# RAMBo.net
KiCad netlist of a schematic drawn in EAGLE
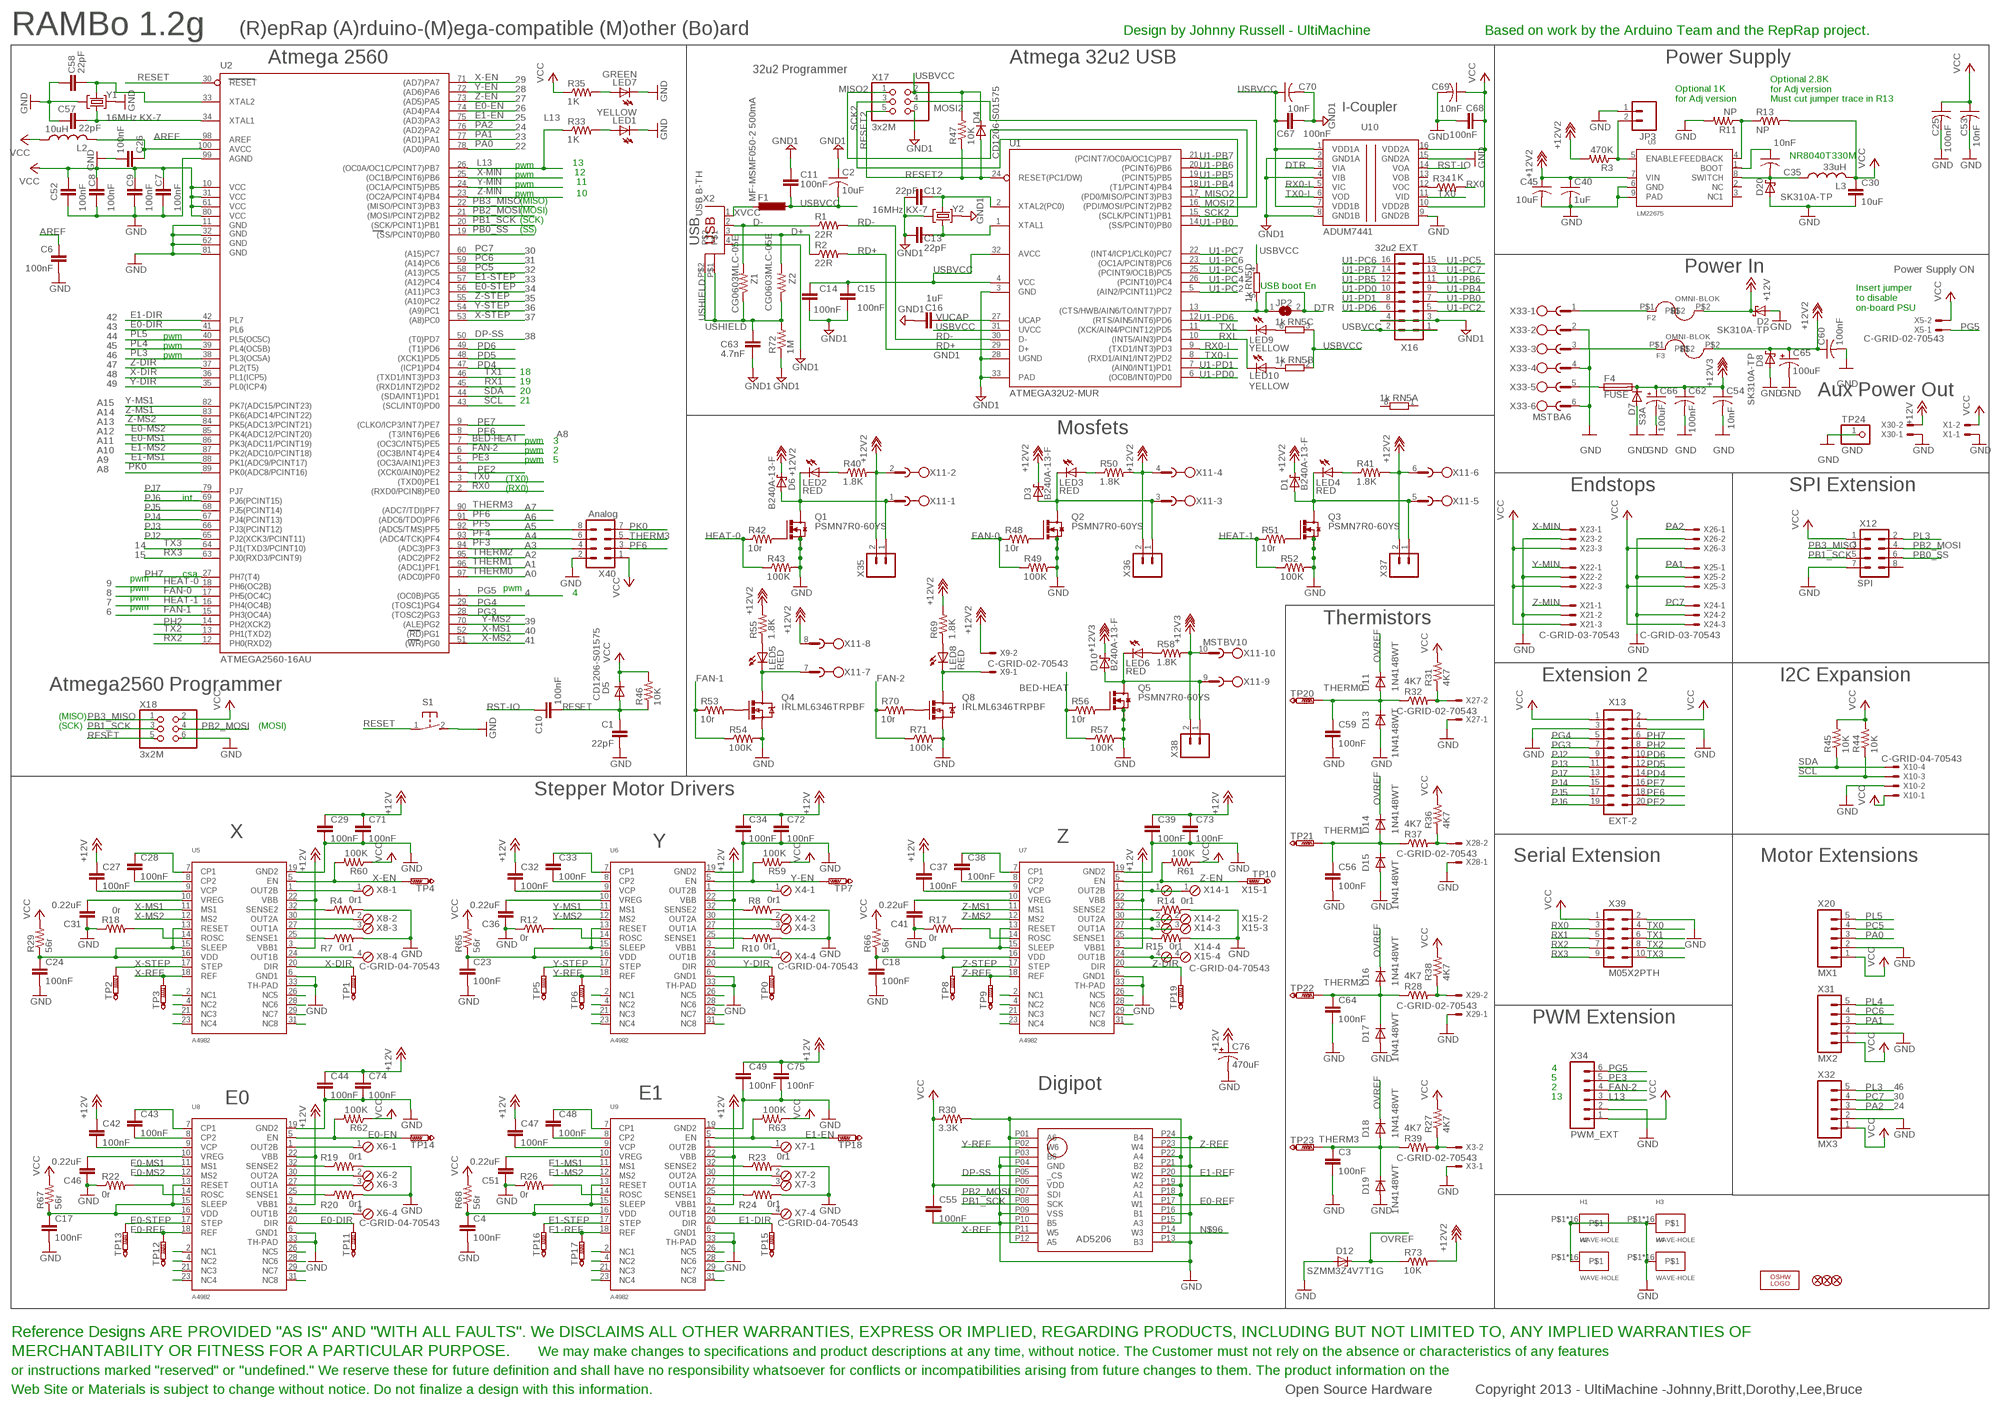
[diagram p0: schematic, sheet 1]

(export (version "E")
  (design (tool "Eeschema 10.0.6"))
  (components
    (comp (ref "C1")
      (value "22pF")
      (footprint "eagle-import:C0603")
      (libsource (lib "eagle-import") (part "resistor_C-EUC0603"))
    )
    (comp (ref "C2")
      (value "10uF")
      (footprint "eagle-import:C0805")
      (libsource (lib "eagle-import") (part "C-USC0805"))
    )
    (comp (ref "C3")
      (value "100nF")
      (footprint "eagle-import:C0603")
      (libsource (lib "eagle-import") (part "resistor_C-EUC0603"))
    )
    (comp (ref "C4")
      (value "100nF")
      (footprint "eagle-import:C0603")
      (libsource (lib "eagle-import") (part "resistor_C-EUC0603"))
    )
    (comp (ref "C6")
      (value "100nF")
      (footprint "eagle-import:C0603")
      (libsource (lib "eagle-import") (part "resistor_C-EUC0603"))
    )
    (comp (ref "C7")
      (value "100nF")
      (footprint "eagle-import:C0603")
      (libsource (lib "eagle-import") (part "resistor_C-EUC0603"))
    )
    (comp (ref "C8")
      (value "100nF")
      (footprint "eagle-import:C0603")
      (libsource (lib "eagle-import") (part "resistor_C-EUC0603"))
    )
    (comp (ref "C9")
      (value "100nF")
      (footprint "eagle-import:C0603")
      (libsource (lib "eagle-import") (part "resistor_C-EUC0603"))
    )
    (comp (ref "C10")
      (value "100nF")
      (footprint "eagle-import:C0603")
      (libsource (lib "eagle-import") (part "resistor_C-EUC0603"))
    )
    (comp (ref "C11")
      (value "100nF")
      (footprint "eagle-import:C0603")
      (libsource (lib "eagle-import") (part "resistor_C-EUC0603"))
    )
    (comp (ref "C12")
      (value "22pF")
      (footprint "eagle-import:C0603")
      (libsource (lib "eagle-import") (part "resistor_C-EUC0603"))
    )
    (comp (ref "C13")
      (value "22pF")
      (footprint "eagle-import:C0603")
      (libsource (lib "eagle-import") (part "resistor_C-EUC0603"))
    )
    (comp (ref "C14")
      (value "100nF")
      (footprint "eagle-import:C0603")
      (libsource (lib "eagle-import") (part "resistor_C-EUC0603"))
    )
    (comp (ref "C15")
      (value "100nF")
      (footprint "eagle-import:C0603")
      (libsource (lib "eagle-import") (part "resistor_C-EUC0603"))
    )
    (comp (ref "C16")
      (value "1uF")
      (footprint "eagle-import:C0603")
      (libsource (lib "eagle-import") (part "resistor_C-EUC0603"))
    )
    (comp (ref "C17")
      (value "100nF")
      (footprint "eagle-import:C0603")
      (libsource (lib "eagle-import") (part "resistor_C-EUC0603"))
    )
    (comp (ref "C18")
      (value "100nF")
      (footprint "eagle-import:C0603")
      (libsource (lib "eagle-import") (part "resistor_C-EUC0603"))
    )
    (comp (ref "C23")
      (value "100nF")
      (footprint "eagle-import:C0603")
      (libsource (lib "eagle-import") (part "resistor_C-EUC0603"))
    )
    (comp (ref "C24")
      (value "100nF")
      (footprint "eagle-import:C0603")
      (libsource (lib "eagle-import") (part "resistor_C-EUC0603"))
    )
    (comp (ref "C25")
      (value "100nF")
      (footprint "eagle-import:C0603")
      (libsource (lib "eagle-import") (part "C-USC0603"))
    )
    (comp (ref "C26")
      (value "100nF")
      (footprint "eagle-import:C0603")
      (libsource (lib "eagle-import") (part "resistor_C-EUC0603"))
    )
    (comp (ref "C27")
      (value "100nF")
      (footprint "eagle-import:C0603")
      (libsource (lib "eagle-import") (part "resistor_C-EUC0603"))
    )
    (comp (ref "C28")
      (value "100nF")
      (footprint "eagle-import:C0603")
      (libsource (lib "eagle-import") (part "resistor_C-EUC0603"))
    )
    (comp (ref "C29")
      (value "100nF")
      (footprint "eagle-import:C0603")
      (libsource (lib "eagle-import") (part "resistor_C-EUC0603"))
    )
    (comp (ref "C30")
      (value "10uF")
      (footprint "eagle-import:C1210K")
      (libsource (lib "eagle-import") (part "resistor_C-EUC1210K"))
    )
    (comp (ref "C31")
      (value "0.22uF")
      (footprint "eagle-import:C0603")
      (libsource (lib "eagle-import") (part "resistor_C-EUC0603"))
    )
    (comp (ref "C32")
      (value "100nF")
      (footprint "eagle-import:C0603")
      (libsource (lib "eagle-import") (part "resistor_C-EUC0603"))
    )
    (comp (ref "C33")
      (value "100nF")
      (footprint "eagle-import:C0603")
      (libsource (lib "eagle-import") (part "resistor_C-EUC0603"))
    )
    (comp (ref "C34")
      (value "100nF")
      (footprint "eagle-import:C0603")
      (libsource (lib "eagle-import") (part "resistor_C-EUC0603"))
    )
    (comp (ref "C35")
      (value "10nF")
      (footprint "eagle-import:C0603")
      (libsource (lib "eagle-import") (part "C-USC0603"))
    )
    (comp (ref "C36")
      (value "0.22uF")
      (footprint "eagle-import:C0603")
      (libsource (lib "eagle-import") (part "resistor_C-EUC0603"))
    )
    (comp (ref "C37")
      (value "100nF")
      (footprint "eagle-import:C0603")
      (libsource (lib "eagle-import") (part "resistor_C-EUC0603"))
    )
    (comp (ref "C38")
      (value "100nF")
      (footprint "eagle-import:C0603")
      (libsource (lib "eagle-import") (part "resistor_C-EUC0603"))
    )
    (comp (ref "C39")
      (value "100nF")
      (footprint "eagle-import:C0603")
      (libsource (lib "eagle-import") (part "resistor_C-EUC0603"))
    )
    (comp (ref "C40")
      (value "1uF")
      (footprint "eagle-import:C0805")
      (libsource (lib "eagle-import") (part "C-USC0805"))
    )
    (comp (ref "C41")
      (value "0.22uF")
      (footprint "eagle-import:C0603")
      (libsource (lib "eagle-import") (part "resistor_C-EUC0603"))
    )
    (comp (ref "C42")
      (value "100nF")
      (footprint "eagle-import:C0603")
      (libsource (lib "eagle-import") (part "resistor_C-EUC0603"))
    )
    (comp (ref "C43")
      (value "100nF")
      (footprint "eagle-import:C0603")
      (libsource (lib "eagle-import") (part "resistor_C-EUC0603"))
    )
    (comp (ref "C44")
      (value "100nF")
      (footprint "eagle-import:C0603")
      (libsource (lib "eagle-import") (part "resistor_C-EUC0603"))
    )
    (comp (ref "C45")
      (value "10uF")
      (footprint "eagle-import:C2220K")
      (libsource (lib "eagle-import") (part "C-USC2220K"))
    )
    (comp (ref "C46")
      (value "0.22uF")
      (footprint "eagle-import:C0603")
      (libsource (lib "eagle-import") (part "resistor_C-EUC0603"))
    )
    (comp (ref "C47")
      (value "100nF")
      (footprint "eagle-import:C0603")
      (libsource (lib "eagle-import") (part "resistor_C-EUC0603"))
    )
    (comp (ref "C48")
      (value "100nF")
      (footprint "eagle-import:C0603")
      (libsource (lib "eagle-import") (part "resistor_C-EUC0603"))
    )
    (comp (ref "C49")
      (value "100nF")
      (footprint "eagle-import:C0603")
      (libsource (lib "eagle-import") (part "resistor_C-EUC0603"))
    )
    (comp (ref "C51")
      (value "0.22uF")
      (footprint "eagle-import:C0603")
      (libsource (lib "eagle-import") (part "resistor_C-EUC0603"))
    )
    (comp (ref "C52")
      (value "100nF")
      (footprint "eagle-import:C0603")
      (libsource (lib "eagle-import") (part "resistor_C-EUC0603"))
    )
    (comp (ref "C53")
      (value "10nF")
      (footprint "eagle-import:C0603")
      (libsource (lib "eagle-import") (part "C-USC0603"))
    )
    (comp (ref "C54")
      (value "10nF")
      (footprint "eagle-import:C0603")
      (libsource (lib "eagle-import") (part "C-USC0603"))
    )
    (comp (ref "C55")
      (value "100nF")
      (footprint "eagle-import:C0603")
      (libsource (lib "eagle-import") (part "resistor_C-EUC0603"))
    )
    (comp (ref "C56")
      (value "100nF")
      (footprint "eagle-import:C0603")
      (libsource (lib "eagle-import") (part "resistor_C-EUC0603"))
    )
    (comp (ref "C57")
      (value "22pF")
      (footprint "eagle-import:C0603")
      (libsource (lib "eagle-import") (part "resistor_C-EUC0603"))
    )
    (comp (ref "C58")
      (value "22pF")
      (footprint "eagle-import:C0603")
      (libsource (lib "eagle-import") (part "resistor_C-EUC0603"))
    )
    (comp (ref "C59")
      (value "100nF")
      (footprint "eagle-import:C0603")
      (libsource (lib "eagle-import") (part "resistor_C-EUC0603"))
    )
    (comp (ref "C60")
      (value "100nF")
      (footprint "eagle-import:C0603")
      (libsource (lib "eagle-import") (part "C-USC0603"))
    )
    (comp (ref "C62")
      (value "100nF")
      (footprint "eagle-import:C0603")
      (libsource (lib "eagle-import") (part "C-USC0603"))
    )
    (comp (ref "C63")
      (value "4.7nF")
      (footprint "eagle-import:C0402")
      (libsource (lib "eagle-import") (part "C-EUC0402"))
    )
    (comp (ref "C64")
      (value "100nF")
      (footprint "eagle-import:C0603")
      (libsource (lib "eagle-import") (part "resistor_C-EUC0603"))
    )
    (comp (ref "C65")
      (value "100uF")
      (footprint "eagle-import:E3,5-8")
      (libsource (lib "eagle-import") (part "CPOL-USE3.5-8"))
    )
    (comp (ref "C66")
      (value "100uF")
      (footprint "eagle-import:E3,5-8")
      (libsource (lib "eagle-import") (part "CPOL-USE3.5-8"))
    )
    (comp (ref "C67")
      (value "100nF")
      (footprint "eagle-import:C0603")
      (libsource (lib "eagle-import") (part "resistor_C-EUC0603"))
    )
    (comp (ref "C68")
      (value "100nF")
      (footprint "eagle-import:C0603")
      (libsource (lib "eagle-import") (part "resistor_C-EUC0603"))
    )
    (comp (ref "C69")
      (value "10nF")
      (footprint "eagle-import:C0603")
      (libsource (lib "eagle-import") (part "C-USC0603"))
    )
    (comp (ref "C70")
      (value "10nF")
      (footprint "eagle-import:C0603")
      (libsource (lib "eagle-import") (part "C-USC0603"))
    )
    (comp (ref "C71")
      (value "100nF")
      (footprint "eagle-import:C0603")
      (libsource (lib "eagle-import") (part "resistor_C-EUC0603"))
    )
    (comp (ref "C72")
      (value "100nF")
      (footprint "eagle-import:C0603")
      (libsource (lib "eagle-import") (part "resistor_C-EUC0603"))
    )
    (comp (ref "C73")
      (value "100nF")
      (footprint "eagle-import:C0603")
      (libsource (lib "eagle-import") (part "resistor_C-EUC0603"))
    )
    (comp (ref "C74")
      (value "100nF")
      (footprint "eagle-import:C0603")
      (libsource (lib "eagle-import") (part "resistor_C-EUC0603"))
    )
    (comp (ref "C75")
      (value "100nF")
      (footprint "eagle-import:C0603")
      (libsource (lib "eagle-import") (part "resistor_C-EUC0603"))
    )
    (comp (ref "C76")
      (value "470uF")
      (footprint "eagle-import:C12,5-5")
      (libsource (lib "eagle-import") (part "CPOL-USC12,5-5"))
    )
    (comp (ref "D1")
      (value "B240A-13-F")
      (footprint "eagle-import:SMA-SM")
      (libsource (lib "eagle-import") (part "SCHOTTKY-DIODE"))
    )
    (comp (ref "D2")
      (value "SK310A-TP")
      (footprint "eagle-import:SMA-SM")
      (libsource (lib "eagle-import") (part "SCHOTTKY-DIODE"))
    )
    (comp (ref "D3")
      (value "B240A-13-F")
      (footprint "eagle-import:SMA-SM")
      (libsource (lib "eagle-import") (part "SCHOTTKY-DIODE"))
    )
    (comp (ref "D4")
      (value "CD1206-S01575")
      (footprint "eagle-import:MINIMELF")
      (libsource (lib "eagle-import") (part "DIODE-MINIMELF"))
    )
    (comp (ref "D5")
      (value "CD1206-S01575")
      (footprint "eagle-import:MINIMELF")
      (libsource (lib "eagle-import") (part "DIODE-MINIMELF"))
    )
    (comp (ref "D6")
      (value "B240A-13-F")
      (footprint "eagle-import:SMA-SM")
      (libsource (lib "eagle-import") (part "SCHOTTKY-DIODE"))
    )
    (comp (ref "D7")
      (value "S3A")
      (footprint "eagle-import:DO-214AB")
      (libsource (lib "eagle-import") (part "DIODE-D0-214AB"))
    )
    (comp (ref "D8")
      (value "SK310A-TP")
      (footprint "eagle-import:SMA-SM")
      (libsource (lib "eagle-import") (part "SCHOTTKY-DIODE"))
    )
    (comp (ref "D10")
      (value "B240A-13-F")
      (footprint "eagle-import:SMA-SM")
      (libsource (lib "eagle-import") (part "SCHOTTKY-DIODE"))
    )
    (comp (ref "D11")
      (value "1N4148WT")
      (footprint "eagle-import:SOD523")
      (libsource (lib "eagle-import") (part "1N4148WT"))
    )
    (comp (ref "D12")
      (value "SZMM3Z4V7T1G")
      (footprint "eagle-import:SOD323-R")
      (libsource (lib "eagle-import") (part "ZENER-DIODESOD323"))
    )
    (comp (ref "D13")
      (value "1N4148WT")
      (footprint "eagle-import:SOD523")
      (libsource (lib "eagle-import") (part "1N4148WT"))
    )
    (comp (ref "D14")
      (value "1N4148WT")
      (footprint "eagle-import:SOD523")
      (libsource (lib "eagle-import") (part "1N4148WT"))
    )
    (comp (ref "D15")
      (value "1N4148WT")
      (footprint "eagle-import:SOD523")
      (libsource (lib "eagle-import") (part "1N4148WT"))
    )
    (comp (ref "D16")
      (value "1N4148WT")
      (footprint "eagle-import:SOD523")
      (libsource (lib "eagle-import") (part "1N4148WT"))
    )
    (comp (ref "D17")
      (value "1N4148WT")
      (footprint "eagle-import:SOD523")
      (libsource (lib "eagle-import") (part "1N4148WT"))
    )
    (comp (ref "D18")
      (value "1N4148WT")
      (footprint "eagle-import:SOD523")
      (libsource (lib "eagle-import") (part "1N4148WT"))
    )
    (comp (ref "D19")
      (value "1N4148WT")
      (footprint "eagle-import:SOD523")
      (libsource (lib "eagle-import") (part "1N4148WT"))
    )
    (comp (ref "D20")
      (value "SK310A-TP")
      (footprint "eagle-import:SMA-SM")
      (libsource (lib "eagle-import") (part "SCHOTTKY-DIODE"))
    )
    (comp (ref "F1")
      (value "MF-MSMF050-2 500mA")
      (footprint "eagle-import:L1812")
      (libsource (lib "eagle-import") (part "L-EUL1812"))
    )
    (comp (ref "F2")
      (value "OMNI-BLOK")
      (footprint "eagle-import:OMNI-BLOK")
      (libsource (lib "eagle-import") (part "OMNI-BLOK"))
    )
    (comp (ref "F3")
      (value "OMNI-BLOK")
      (footprint "eagle-import:OMNI-BLOK")
      (libsource (lib "eagle-import") (part "OMNI-BLOK"))
    )
    (comp (ref "F4")
      (value "FUSE")
      (footprint "eagle-import:FUSE-ATO-SMD")
      (libsource (lib "eagle-import") (part "FUSE"))
    )
    (comp (ref "FID1")
      (value "FIDUCIAL1X2")
      (footprint "eagle-import:FIDUCIAL-1X2")
      (libsource (lib "eagle-import") (part "FIDUCIAL1X2"))
    )
    (comp (ref "FID2")
      (value "FIDUCIAL1X2")
      (footprint "eagle-import:FIDUCIAL-1X2")
      (libsource (lib "eagle-import") (part "FIDUCIAL1X2"))
    )
    (comp (ref "FID3")
      (value "FIDUCIAL1X2")
      (footprint "eagle-import:FIDUCIAL-1X2")
      (libsource (lib "eagle-import") (part "FIDUCIAL1X2"))
    )
    (comp (ref "H1")
      (value "WAVE-HOLE")
      (footprint "eagle-import:3,0-WAVE-HOLE")
      (libsource (lib "eagle-import") (part "WAVE-HOLE"))
    )
    (comp (ref "H2")
      (value "WAVE-HOLE")
      (footprint "eagle-import:3,0-WAVE-HOLE")
      (libsource (lib "eagle-import") (part "WAVE-HOLE"))
    )
    (comp (ref "H3")
      (value "WAVE-HOLE")
      (footprint "eagle-import:3,0-WAVE-HOLE")
      (libsource (lib "eagle-import") (part "WAVE-HOLE"))
    )
    (comp (ref "H4")
      (value "WAVE-HOLE")
      (footprint "eagle-import:3,0-WAVE-HOLE")
      (libsource (lib "eagle-import") (part "WAVE-HOLE"))
    )
    (comp (ref "JP2") (value "SJ") (footprint "eagle-import:SJ") (libsource (lib "eagle-import") (part "SJ")))
    (comp (ref "JP3")
      (value "M02PTH")
      (footprint "eagle-import:1X02")
      (libsource (lib "eagle-import") (part "M02PTH"))
    )
    (comp (ref "L2")
      (value "10uH")
      (footprint "eagle-import:C0805")
      (libsource (lib "eagle-import") (part "L-US"))
    )
    (comp (ref "L3")
      (value "33uH")
      (footprint "eagle-import:NR8040")
      (libsource (lib "eagle-import") (part "L-USNR8040"))
    )
    (comp (ref "LED1")
      (value "YELLOW")
      (footprint "eagle-import:CHIP-LED0805")
      (libsource (lib "eagle-import") (part "LEDCHIP-LED0805"))
    )
    (comp (ref "LED2")
      (value "RED")
      (footprint "eagle-import:CHIP-LED0805")
      (libsource (lib "eagle-import") (part "LEDCHIP-LED0805"))
    )
    (comp (ref "LED3")
      (value "RED")
      (footprint "eagle-import:CHIP-LED0805")
      (libsource (lib "eagle-import") (part "LEDCHIP-LED0805"))
    )
    (comp (ref "LED4")
      (value "RED")
      (footprint "eagle-import:CHIP-LED0805")
      (libsource (lib "eagle-import") (part "LEDCHIP-LED0805"))
    )
    (comp (ref "LED5")
      (value "RED")
      (footprint "eagle-import:CHIP-LED0805")
      (libsource (lib "eagle-import") (part "LEDCHIP-LED0805"))
    )
    (comp (ref "LED6")
      (value "RED")
      (footprint "eagle-import:CHIP-LED0805")
      (libsource (lib "eagle-import") (part "LEDCHIP-LED0805"))
    )
    (comp (ref "LED7")
      (value "GREEN")
      (footprint "eagle-import:CHIP-LED0805")
      (libsource (lib "eagle-import") (part "LEDCHIP-LED0805"))
    )
    (comp (ref "LED8")
      (value "RED")
      (footprint "eagle-import:CHIP-LED0805")
      (libsource (lib "eagle-import") (part "LEDCHIP-LED0805"))
    )
    (comp (ref "LED9")
      (value "YELLOW")
      (footprint "eagle-import:CHIP-LED0805")
      (libsource (lib "eagle-import") (part "LEDCHIP-LED0805"))
    )
    (comp (ref "LED10")
      (value "YELLOW")
      (footprint "eagle-import:CHIP-LED0805")
      (libsource (lib "eagle-import") (part "LEDCHIP-LED0805"))
    )
    (comp (ref "LOGO1")
      (value "OSHW_LOGO_8MILX0150-NT")
      (footprint "eagle-import:OSHW_8X150_NOTEXT")
      (libsource (lib "eagle-import") (part "OSHW_LOGO_8MILX0150-NT"))
    )
    (comp (ref "Q1")
      (value "PSMN7R0-60YS")
      (footprint "eagle-import:SOT669")
      (libsource (lib "eagle-import") (part "PH7030L"))
    )
    (comp (ref "Q2")
      (value "PSMN7R0-60YS")
      (footprint "eagle-import:SOT669")
      (libsource (lib "eagle-import") (part "PH7030L"))
    )
    (comp (ref "Q3")
      (value "PSMN7R0-60YS")
      (footprint "eagle-import:SOT669")
      (libsource (lib "eagle-import") (part "PH7030L"))
    )
    (comp (ref "Q4")
      (value "IRLML6346TRPBF")
      (footprint "eagle-import:SOT23-3")
      (libsource (lib "eagle-import") (part "MOSFET-NCHANNELSMD"))
    )
    (comp (ref "Q5")
      (value "PSMN7R0-60YS")
      (footprint "eagle-import:SOT669")
      (libsource (lib "eagle-import") (part "PH7030L"))
    )
    (comp (ref "Q8")
      (value "IRLML6346TRPBF")
      (footprint "eagle-import:SOT23-3")
      (libsource (lib "eagle-import") (part "MOSFET-NCHANNELSMD"))
    )
    (comp (ref "R1")
      (value "22R")
      (footprint "eagle-import:R0402")
      (libsource (lib "eagle-import") (part "R-US_R0402"))
    )
    (comp (ref "R2")
      (value "22R")
      (footprint "eagle-import:R0402")
      (libsource (lib "eagle-import") (part "R-US_R0402"))
    )
    (comp (ref "R3")
      (value "470K")
      (footprint "eagle-import:R0603")
      (libsource (lib "eagle-import") (part "resistor_R-US_R0603"))
    )
    (comp (ref "R4")
      (value "0r1")
      (footprint "eagle-import:R1206")
      (libsource (lib "eagle-import") (part "resistor_R-US_R1206"))
    )
    (comp (ref "R7")
      (value "0r1")
      (footprint "eagle-import:R1206")
      (libsource (lib "eagle-import") (part "resistor_R-US_R1206"))
    )
    (comp (ref "R8")
      (value "0r1")
      (footprint "eagle-import:R1206")
      (libsource (lib "eagle-import") (part "resistor_R-US_R1206"))
    )
    (comp (ref "R10")
      (value "0r1")
      (footprint "eagle-import:R1206")
      (libsource (lib "eagle-import") (part "resistor_R-US_R1206"))
    )
    (comp (ref "R11")
      (value "NP")
      (footprint "eagle-import:R0603")
      (libsource (lib "eagle-import") (part "resistor_R-US_R0603"))
    )
    (comp (ref "R12")
      (value "0r")
      (footprint "eagle-import:R0603")
      (libsource (lib "eagle-import") (part "resistor_R-US_R0603"))
    )
    (comp (ref "R13")
      (value "NP")
      (footprint "eagle-import:R0603")
      (libsource (lib "eagle-import") (part "resistor_R-US_R0603"))
    )
    (comp (ref "R14")
      (value "0r1")
      (footprint "eagle-import:R1206")
      (libsource (lib "eagle-import") (part "resistor_R-US_R1206"))
    )
    (comp (ref "R15")
      (value "0r1")
      (footprint "eagle-import:R1206")
      (libsource (lib "eagle-import") (part "resistor_R-US_R1206"))
    )
    (comp (ref "R17")
      (value "0r")
      (footprint "eagle-import:R0603")
      (libsource (lib "eagle-import") (part "resistor_R-US_R0603"))
    )
    (comp (ref "R18")
      (value "0r")
      (footprint "eagle-import:R0603")
      (libsource (lib "eagle-import") (part "resistor_R-US_R0603"))
    )
    (comp (ref "R19")
      (value "0r1")
      (footprint "eagle-import:R1206")
      (libsource (lib "eagle-import") (part "resistor_R-US_R1206"))
    )
    (comp (ref "R20")
      (value "0r1")
      (footprint "eagle-import:R1206")
      (libsource (lib "eagle-import") (part "resistor_R-US_R1206"))
    )
    (comp (ref "R22")
      (value "0r")
      (footprint "eagle-import:R0603")
      (libsource (lib "eagle-import") (part "resistor_R-US_R0603"))
    )
    (comp (ref "R23")
      (value "0r1")
      (footprint "eagle-import:R1206")
      (libsource (lib "eagle-import") (part "resistor_R-US_R1206"))
    )
    (comp (ref "R24")
      (value "0r1")
      (footprint "eagle-import:R1206")
      (libsource (lib "eagle-import") (part "resistor_R-US_R1206"))
    )
    (comp (ref "R26")
      (value "0r")
      (footprint "eagle-import:R0603")
      (libsource (lib "eagle-import") (part "resistor_R-US_R0603"))
    )
    (comp (ref "R27")
      (value "4K7")
      (footprint "eagle-import:R0603")
      (libsource (lib "eagle-import") (part "resistor_R-US_R0603"))
    )
    (comp (ref "R28")
      (value "4K7")
      (footprint "eagle-import:R0603")
      (libsource (lib "eagle-import") (part "resistor_R-US_R0603"))
    )
    (comp (ref "R29")
      (value "56r")
      (footprint "eagle-import:R0603")
      (libsource (lib "eagle-import") (part "resistor_R-US_R0603"))
    )
    (comp (ref "R30")
      (value "3.3K")
      (footprint "eagle-import:R0603")
      (libsource (lib "eagle-import") (part "resistor_R-US_R0603"))
    )
    (comp (ref "R31")
      (value "4K7")
      (footprint "eagle-import:R0603")
      (libsource (lib "eagle-import") (part "resistor_R-US_R0603"))
    )
    (comp (ref "R32")
      (value "4K7")
      (footprint "eagle-import:R0603")
      (libsource (lib "eagle-import") (part "resistor_R-US_R0603"))
    )
    (comp (ref "R33")
      (value "1K")
      (footprint "eagle-import:R0603")
      (libsource (lib "eagle-import") (part "resistor_R-US_R0603"))
    )
    (comp (ref "R34")
      (value "1K")
      (footprint "eagle-import:R0603")
      (libsource (lib "eagle-import") (part "resistor_R-US_R0603"))
    )
    (comp (ref "R35")
      (value "1K")
      (footprint "eagle-import:R0603")
      (libsource (lib "eagle-import") (part "resistor_R-US_R0603"))
    )
    (comp (ref "R36")
      (value "4K7")
      (footprint "eagle-import:R0603")
      (libsource (lib "eagle-import") (part "resistor_R-US_R0603"))
    )
    (comp (ref "R37")
      (value "4K7")
      (footprint "eagle-import:R0603")
      (libsource (lib "eagle-import") (part "resistor_R-US_R0603"))
    )
    (comp (ref "R38")
      (value "4K7")
      (footprint "eagle-import:R0603")
      (libsource (lib "eagle-import") (part "resistor_R-US_R0603"))
    )
    (comp (ref "R39")
      (value "4K7")
      (footprint "eagle-import:R0603")
      (libsource (lib "eagle-import") (part "resistor_R-US_R0603"))
    )
    (comp (ref "R40")
      (value "1.8K")
      (footprint "eagle-import:R0603")
      (libsource (lib "eagle-import") (part "resistor_R-US_R0603"))
    )
    (comp (ref "R41")
      (value "1.8K")
      (footprint "eagle-import:R0603")
      (libsource (lib "eagle-import") (part "resistor_R-US_R0603"))
    )
    (comp (ref "R42")
      (value "10r")
      (footprint "eagle-import:R0603")
      (libsource (lib "eagle-import") (part "resistor_R-US_R0603"))
    )
    (comp (ref "R43")
      (value "100K")
      (footprint "eagle-import:R0603")
      (libsource (lib "eagle-import") (part "resistor_R-US_R0603"))
    )
    (comp (ref "R44")
      (value "10K")
      (footprint "eagle-import:R0603")
      (libsource (lib "eagle-import") (part "resistor_R-US_R0603"))
    )
    (comp (ref "R45")
      (value "10K")
      (footprint "eagle-import:R0603")
      (libsource (lib "eagle-import") (part "resistor_R-US_R0603"))
    )
    (comp (ref "R46")
      (value "10K")
      (footprint "eagle-import:R0603")
      (libsource (lib "eagle-import") (part "resistor_R-US_R0603"))
    )
    (comp (ref "R47")
      (value "10K")
      (footprint "eagle-import:R0603")
      (libsource (lib "eagle-import") (part "resistor_R-US_R0603"))
    )
    (comp (ref "R48")
      (value "10r")
      (footprint "eagle-import:R0603")
      (libsource (lib "eagle-import") (part "resistor_R-US_R0603"))
    )
    (comp (ref "R49")
      (value "100K")
      (footprint "eagle-import:R0603")
      (libsource (lib "eagle-import") (part "resistor_R-US_R0603"))
    )
    (comp (ref "R50")
      (value "1.8K")
      (footprint "eagle-import:R0603")
      (libsource (lib "eagle-import") (part "resistor_R-US_R0603"))
    )
    (comp (ref "R51")
      (value "10r")
      (footprint "eagle-import:R0603")
      (libsource (lib "eagle-import") (part "resistor_R-US_R0603"))
    )
    (comp (ref "R52")
      (value "100K")
      (footprint "eagle-import:R0603")
      (libsource (lib "eagle-import") (part "resistor_R-US_R0603"))
    )
    (comp (ref "R53")
      (value "10r")
      (footprint "eagle-import:R0603")
      (libsource (lib "eagle-import") (part "resistor_R-US_R0603"))
    )
    (comp (ref "R54")
      (value "100K")
      (footprint "eagle-import:R0603")
      (libsource (lib "eagle-import") (part "resistor_R-US_R0603"))
    )
    (comp (ref "R55")
      (value "1.8K")
      (footprint "eagle-import:R0603")
      (libsource (lib "eagle-import") (part "resistor_R-US_R0603"))
    )
    (comp (ref "R56")
      (value "10r")
      (footprint "eagle-import:R0603")
      (libsource (lib "eagle-import") (part "resistor_R-US_R0603"))
    )
    (comp (ref "R57")
      (value "100K")
      (footprint "eagle-import:R0603")
      (libsource (lib "eagle-import") (part "resistor_R-US_R0603"))
    )
    (comp (ref "R58")
      (value "1.8K")
      (footprint "eagle-import:R0603")
      (libsource (lib "eagle-import") (part "resistor_R-US_R0603"))
    )
    (comp (ref "R59")
      (value "100K")
      (footprint "eagle-import:R0603")
      (libsource (lib "eagle-import") (part "resistor_R-US_R0603"))
    )
    (comp (ref "R60")
      (value "100K")
      (footprint "eagle-import:R0603")
      (libsource (lib "eagle-import") (part "resistor_R-US_R0603"))
    )
    (comp (ref "R61")
      (value "100K")
      (footprint "eagle-import:R0603")
      (libsource (lib "eagle-import") (part "resistor_R-US_R0603"))
    )
    (comp (ref "R62")
      (value "100K")
      (footprint "eagle-import:R0603")
      (libsource (lib "eagle-import") (part "resistor_R-US_R0603"))
    )
    (comp (ref "R63")
      (value "100K")
      (footprint "eagle-import:R0603")
      (libsource (lib "eagle-import") (part "resistor_R-US_R0603"))
    )
    (comp (ref "R65")
      (value "56r")
      (footprint "eagle-import:R0603")
      (libsource (lib "eagle-import") (part "resistor_R-US_R0603"))
    )
    (comp (ref "R66")
      (value "56r")
      (footprint "eagle-import:R0603")
      (libsource (lib "eagle-import") (part "resistor_R-US_R0603"))
    )
    (comp (ref "R67")
      (value "56r")
      (footprint "eagle-import:R0603")
      (libsource (lib "eagle-import") (part "resistor_R-US_R0603"))
    )
    (comp (ref "R68")
      (value "56r")
      (footprint "eagle-import:R0603")
      (libsource (lib "eagle-import") (part "resistor_R-US_R0603"))
    )
    (comp (ref "R69")
      (value "1.8K")
      (footprint "eagle-import:R0603")
      (libsource (lib "eagle-import") (part "resistor_R-US_R0603"))
    )
    (comp (ref "R70")
      (value "10r")
      (footprint "eagle-import:R0603")
      (libsource (lib "eagle-import") (part "resistor_R-US_R0603"))
    )
    (comp (ref "R71")
      (value "100K")
      (footprint "eagle-import:R0603")
      (libsource (lib "eagle-import") (part "resistor_R-US_R0603"))
    )
    (comp (ref "R72")
      (value "1M")
      (footprint "eagle-import:R0402")
      (libsource (lib "eagle-import") (part "R-US_R0402"))
    )
    (comp (ref "R73")
      (value "10K")
      (footprint "eagle-import:R0603")
      (libsource (lib "eagle-import") (part "resistor_R-US_R0603"))
    )
    (comp (ref "RN5")
      (value "1k")
      (footprint "eagle-import:CAY16")
      (libsource (lib "eagle-import") (part "4R-NCAY16"))
    )
    (comp (ref "S1")
      (value "31-XX")
      (footprint "eagle-import:B3F-31XX")
      (libsource (lib "eagle-import") (part "31-XX"))
    )
    (comp (ref "TP0")
      (value "PTR1B1,27TH")
      (footprint "eagle-import:B1,27TH")
      (libsource (lib "eagle-import") (part "PTR1B1,27TH"))
    )
    (comp (ref "TP1")
      (value "PTR1B1,27TH")
      (footprint "eagle-import:B1,27TH")
      (libsource (lib "eagle-import") (part "PTR1B1,27TH"))
    )
    (comp (ref "TP2")
      (value "PTR1B1,27TH")
      (footprint "eagle-import:B1,27TH")
      (libsource (lib "eagle-import") (part "PTR1B1,27TH"))
    )
    (comp (ref "TP3")
      (value "PTR1B1,27TH")
      (footprint "eagle-import:B1,27TH")
      (libsource (lib "eagle-import") (part "PTR1B1,27TH"))
    )
    (comp (ref "TP4")
      (value "PTR1B1,27TH")
      (footprint "eagle-import:B1,27TH")
      (libsource (lib "eagle-import") (part "PTR1B1,27TH"))
    )
    (comp (ref "TP5")
      (value "PTR1B1,27TH")
      (footprint "eagle-import:B1,27TH")
      (libsource (lib "eagle-import") (part "PTR1B1,27TH"))
    )
    (comp (ref "TP6")
      (value "PTR1B1,27TH")
      (footprint "eagle-import:B1,27TH")
      (libsource (lib "eagle-import") (part "PTR1B1,27TH"))
    )
    (comp (ref "TP7")
      (value "PTR1B1,27TH")
      (footprint "eagle-import:B1,27TH")
      (libsource (lib "eagle-import") (part "PTR1B1,27TH"))
    )
    (comp (ref "TP8")
      (value "PTR1B1,27TH")
      (footprint "eagle-import:B1,27TH")
      (libsource (lib "eagle-import") (part "PTR1B1,27TH"))
    )
    (comp (ref "TP9")
      (value "PTR1B1,27TH")
      (footprint "eagle-import:B1,27TH")
      (libsource (lib "eagle-import") (part "PTR1B1,27TH"))
    )
    (comp (ref "TP10")
      (value "PTR1B1,27TH")
      (footprint "eagle-import:B1,27TH")
      (libsource (lib "eagle-import") (part "PTR1B1,27TH"))
    )
    (comp (ref "TP11")
      (value "PTR1B1,27TH")
      (footprint "eagle-import:B1,27TH")
      (libsource (lib "eagle-import") (part "PTR1B1,27TH"))
    )
    (comp (ref "TP12")
      (value "PTR1B1,27TH")
      (footprint "eagle-import:B1,27TH")
      (libsource (lib "eagle-import") (part "PTR1B1,27TH"))
    )
    (comp (ref "TP13")
      (value "PTR1B1,27TH")
      (footprint "eagle-import:B1,27TH")
      (libsource (lib "eagle-import") (part "PTR1B1,27TH"))
    )
    (comp (ref "TP14")
      (value "PTR1B1,27TH")
      (footprint "eagle-import:B1,27TH")
      (libsource (lib "eagle-import") (part "PTR1B1,27TH"))
    )
    (comp (ref "TP15")
      (value "PTR1B1,27TH")
      (footprint "eagle-import:B1,27TH")
      (libsource (lib "eagle-import") (part "PTR1B1,27TH"))
    )
    (comp (ref "TP16")
      (value "PTR1B1,27TH")
      (footprint "eagle-import:B1,27TH")
      (libsource (lib "eagle-import") (part "PTR1B1,27TH"))
    )
    (comp (ref "TP17")
      (value "PTR1B1,27TH")
      (footprint "eagle-import:B1,27TH")
      (libsource (lib "eagle-import") (part "PTR1B1,27TH"))
    )
    (comp (ref "TP18")
      (value "PTR1B1,27TH")
      (footprint "eagle-import:B1,27TH")
      (libsource (lib "eagle-import") (part "PTR1B1,27TH"))
    )
    (comp (ref "TP19")
      (value "PTR1B1,27TH")
      (footprint "eagle-import:B1,27TH")
      (libsource (lib "eagle-import") (part "PTR1B1,27TH"))
    )
    (comp (ref "TP20")
      (value "PTR1B1,27")
      (footprint "eagle-import:B1,27")
      (libsource (lib "eagle-import") (part "PTR1B1,27"))
    )
    (comp (ref "TP21")
      (value "PTR1B1,27")
      (footprint "eagle-import:B1,27")
      (libsource (lib "eagle-import") (part "PTR1B1,27"))
    )
    (comp (ref "TP22")
      (value "PTR1B1,27")
      (footprint "eagle-import:B1,27")
      (libsource (lib "eagle-import") (part "PTR1B1,27"))
    )
    (comp (ref "TP23")
      (value "PTR1B1,27")
      (footprint "eagle-import:B1,27")
      (libsource (lib "eagle-import") (part "PTR1B1,27"))
    )
    (comp (ref "TP24")
      (value "GND")
      (footprint "eagle-import:1X01")
      (libsource (lib "eagle-import") (part "PINHD-1X1"))
    )
    (comp (ref "U1")
      (value "ATMEGA32U2-MUR")
      (footprint "eagle-import:QFN32TROUND")
      (libsource (lib "eagle-import") (part "ATMEGA16U2-MU2"))
    )
    (comp (ref "U2")
      (value "ATMEGA2560-16AU")
      (footprint "eagle-import:TQFP100")
      (libsource (lib "eagle-import") (part "ATMEGA2560AU2560-16"))
    )
    (comp (ref "U3")
      (value "LM22675")
      (footprint "eagle-import:SOIC127P600X170-9N")
      (libsource (lib "eagle-import") (part "LM22675"))
    )
    (comp (ref "U4")
      (value "AD5206")
      (footprint "eagle-import:TSSOP24")
      (libsource (lib "eagle-import") (part "AD5206"))
    )
    (comp (ref "U5")
      (value "A4982")
      (footprint "eagle-import:QFN32TROUND")
      (libsource (lib "eagle-import") (part "A4982QFN32ROUNDPADS"))
    )
    (comp (ref "U6")
      (value "A4982")
      (footprint "eagle-import:QFN32TROUND")
      (libsource (lib "eagle-import") (part "A4982QFN32ROUNDPADS"))
    )
    (comp (ref "U7")
      (value "A4982")
      (footprint "eagle-import:QFN32TROUND")
      (libsource (lib "eagle-import") (part "A4982QFN32ROUNDPADS"))
    )
    (comp (ref "U8")
      (value "A4982")
      (footprint "eagle-import:QFN32TROUND")
      (libsource (lib "eagle-import") (part "A4982QFN32ROUNDPADS"))
    )
    (comp (ref "U9")
      (value "A4982")
      (footprint "eagle-import:QFN32TROUND")
      (libsource (lib "eagle-import") (part "A4982QFN32ROUNDPADS"))
    )
    (comp (ref "U10")
      (value "ADUM7441")
      (footprint "eagle-import:QSOP16")
      (libsource (lib "eagle-import") (part "ADUM7441"))
    )
    (comp (ref "X1")
      (value "C-GRID-02-70543")
      (footprint "eagle-import:70543-02")
      (libsource (lib "eagle-import") (part "C-GRID-02-70543"))
    )
    (comp (ref "X2")
      (value "USB B-TH")
      (footprint "eagle-import:PN61729")
      (libsource (lib "eagle-import") (part "PN61729"))
    )
    (comp (ref "X3")
      (value "C-GRID-02-70543")
      (footprint "eagle-import:70543-02")
      (libsource (lib "eagle-import") (part "C-GRID-02-70543"))
    )
    (comp (ref "X4")
      (value "C-GRID-04-70543")
      (footprint "eagle-import:4POL254")
      (libsource (lib "eagle-import") (part "MPT4"))
    )
    (comp (ref "X5")
      (value "C-GRID-02-70543")
      (footprint "eagle-import:70543-02")
      (libsource (lib "eagle-import") (part "C-GRID-02-70543"))
    )
    (comp (ref "X6")
      (value "C-GRID-04-70543")
      (footprint "eagle-import:4POL254")
      (libsource (lib "eagle-import") (part "MPT4"))
    )
    (comp (ref "X7")
      (value "C-GRID-04-70543")
      (footprint "eagle-import:4POL254")
      (libsource (lib "eagle-import") (part "MPT4"))
    )
    (comp (ref "X8")
      (value "C-GRID-04-70543")
      (footprint "eagle-import:4POL254")
      (libsource (lib "eagle-import") (part "MPT4"))
    )
    (comp (ref "X9")
      (value "C-GRID-02-70543")
      (footprint "eagle-import:70543-02")
      (fields (field (name "OC_FARNELL") "unknown") (field (name "OC_NEWARK") "unknown"))
      (libsource (lib "eagle-import") (part "C-GRID-02-70543"))
    )
    (comp (ref "X10")
      (value "C-GRID-04-70543")
      (footprint "eagle-import:70543-04")
      (libsource (lib "eagle-import") (part "C-GRID-04-70543"))
    )
    (comp (ref "X11")
      (value "MSTBV10")
      (footprint "eagle-import:MSTBV10")
      (fields (field (name "MPN") "MSTBV 2,5/10-GF-5.08"))
      (libsource (lib "eagle-import") (part "MSTBV10"))
    )
    (comp (ref "X12")
      (value "SPI")
      (footprint "eagle-import:2X4")
      (libsource (lib "eagle-import") (part "M04X2"))
    )
    (comp (ref "X13")
      (value "EXT-2")
      (footprint "eagle-import:2X10")
      (libsource (lib "eagle-import") (part "M10X2"))
    )
    (comp (ref "X14")
      (value "C-GRID-04-70543")
      (footprint "eagle-import:4POL254")
      (libsource (lib "eagle-import") (part "MPT4"))
    )
    (comp (ref "X15")
      (value "C-GRID-04-70543")
      (footprint "eagle-import:4POL254")
      (fields (field (name "OC_FARNELL") "unknown") (field (name "OC_NEWARK") "unknown"))
      (libsource (lib "eagle-import") (part "MPT4"))
    )
    (comp (ref "X16")
      (value "32u2 EXT")
      (footprint "eagle-import:2X8")
      (libsource (lib "eagle-import") (part "M08X2"))
    )
    (comp (ref "X17")
      (value "3x2M")
      (footprint "eagle-import:2X03")
      (libsource (lib "eagle-import") (part "PINHD-2X3"))
    )
    (comp (ref "X18")
      (value "3x2M")
      (footprint "eagle-import:2X03")
      (libsource (lib "eagle-import") (part "PINHD-2X3"))
    )
    (comp (ref "X20")
      (value "MX1")
      (footprint "eagle-import:1X05")
      (libsource (lib "eagle-import") (part "M05PTH"))
    )
    (comp (ref "X21")
      (value "C-GRID-03-70543")
      (footprint "eagle-import:70543-03")
      (libsource (lib "eagle-import") (part "C-GRID-03-70543"))
    )
    (comp (ref "X22")
      (value "C-GRID-03-70543")
      (footprint "eagle-import:70543-03")
      (libsource (lib "eagle-import") (part "C-GRID-03-70543"))
    )
    (comp (ref "X23")
      (value "C-GRID-03-70543")
      (footprint "eagle-import:70543-03")
      (libsource (lib "eagle-import") (part "C-GRID-03-70543"))
    )
    (comp (ref "X24")
      (value "C-GRID-03-70543")
      (footprint "eagle-import:70543-03")
      (libsource (lib "eagle-import") (part "C-GRID-03-70543"))
    )
    (comp (ref "X25")
      (value "C-GRID-03-70543")
      (footprint "eagle-import:70543-03")
      (libsource (lib "eagle-import") (part "C-GRID-03-70543"))
    )
    (comp (ref "X26")
      (value "C-GRID-03-70543")
      (footprint "eagle-import:70543-03")
      (libsource (lib "eagle-import") (part "C-GRID-03-70543"))
    )
    (comp (ref "X27")
      (value "C-GRID-02-70543")
      (footprint "eagle-import:70543-02")
      (libsource (lib "eagle-import") (part "C-GRID-02-70543"))
    )
    (comp (ref "X28")
      (value "C-GRID-02-70543")
      (footprint "eagle-import:70543-02")
      (libsource (lib "eagle-import") (part "C-GRID-02-70543"))
    )
    (comp (ref "X29")
      (value "C-GRID-02-70543")
      (footprint "eagle-import:70543-02")
      (libsource (lib "eagle-import") (part "C-GRID-02-70543"))
    )
    (comp (ref "X30")
      (value "C-GRID-02-70543")
      (footprint "eagle-import:70543-02")
      (libsource (lib "eagle-import") (part "C-GRID-02-70543"))
    )
    (comp (ref "X31")
      (value "MX2")
      (footprint "eagle-import:1X05")
      (libsource (lib "eagle-import") (part "M05PTH"))
    )
    (comp (ref "X32")
      (value "MX3")
      (footprint "eagle-import:1X05")
      (libsource (lib "eagle-import") (part "M05PTH"))
    )
    (comp (ref "X33")
      (value "MSTBA6")
      (footprint "eagle-import:MSTBA6")
      (fields (field (name "MF") "FARNELL") (field (name "MPN") "1757284"))
      (libsource (lib "eagle-import") (part "MSTBA6"))
    )
    (comp (ref "X34")
      (value "PWM_EXT")
      (footprint "eagle-import:1X06")
      (libsource (lib "eagle-import") (part "M06SIP"))
    )
    (comp (ref "X35")
      (value "M02PTH")
      (footprint "eagle-import:1X02")
      (libsource (lib "eagle-import") (part "M02PTH"))
    )
    (comp (ref "X36")
      (value "M02PTH")
      (footprint "eagle-import:1X02")
      (libsource (lib "eagle-import") (part "M02PTH"))
    )
    (comp (ref "X37")
      (value "M02PTH")
      (footprint "eagle-import:1X02")
      (libsource (lib "eagle-import") (part "M02PTH"))
    )
    (comp (ref "X38")
      (value "M02PTH")
      (footprint "eagle-import:1X02")
      (libsource (lib "eagle-import") (part "M02PTH"))
    )
    (comp (ref "X39")
      (value "M05X2PTH")
      (footprint "eagle-import:AVR_ICSP")
      (libsource (lib "eagle-import") (part "M05X2PTH"))
    )
    (comp (ref "X40")
      (value "Analog")
      (footprint "eagle-import:2X4")
      (libsource (lib "eagle-import") (part "M04X2"))
    )
    (comp (ref "Y1")
      (value "16MHz KX-7")
      (footprint "eagle-import:CRYSTAL-3.2-2.5")
      (libsource (lib "eagle-import") (part "CRYSTAL-3.2-2.5"))
    )
    (comp (ref "Y2")
      (value "16MHz KX-7")
      (footprint "eagle-import:CRYSTAL-3.2-2.5")
      (libsource (lib "eagle-import") (part "CRYSTAL-3.2-2.5"))
    )
    (comp (ref "Z1")
      (value "CG0603MLC-05E")
      (footprint "eagle-import:R0603")
      (libsource (lib "eagle-import") (part "resistor_R-US_R0603"))
    )
    (comp (ref "Z2")
      (value "CG0603MLC-05E")
      (footprint "eagle-import:R0603")
      (libsource (lib "eagle-import") (part "resistor_R-US_R0603"))
    )
  )
  (nets
    (net (code "1") (name "+12V") (class "Default")
      (node (ref "C27") (pin "1") (pinfunction "1_1") (pintype "passive"))
      (node (ref "C29") (pin "1") (pinfunction "1_1") (pintype "passive"))
      (node (ref "C32") (pin "1") (pinfunction "1_1") (pintype "passive"))
      (node (ref "C34") (pin "1") (pinfunction "1_1") (pintype "passive"))
      (node (ref "C37") (pin "1") (pinfunction "1_1") (pintype "passive"))
      (node (ref "C39") (pin "1") (pinfunction "1_1") (pintype "passive"))
      (node (ref "C42") (pin "1") (pinfunction "1_1") (pintype "passive"))
      (node (ref "C44") (pin "1") (pinfunction "1_1") (pintype "passive"))
      (node (ref "C47") (pin "1") (pinfunction "1_1") (pintype "passive"))
      (node (ref "C49") (pin "1") (pinfunction "1_1") (pintype "passive"))
      (node (ref "C71") (pin "1") (pinfunction "1_1") (pintype "passive"))
      (node (ref "C72") (pin "1") (pinfunction "1_1") (pintype "passive"))
      (node (ref "C73") (pin "1") (pinfunction "1_1") (pintype "passive"))
      (node (ref "C74") (pin "1") (pinfunction "1_1") (pintype "passive"))
      (node (ref "C75") (pin "1") (pinfunction "1_1") (pintype "passive"))
      (node (ref "C76") (pin "+") (pinfunction "+_+") (pintype "passive"))
      (node (ref "D2") (pin "C") (pinfunction "C_C") (pintype "passive"))
      (node (ref "F2") (pin "P$2") (pinfunction "P$2_P$2") (pintype "bidirectional"))
      (node (ref "U5") (pin "22") (pinfunction "VBB_22") (pintype "power_in"))
      (node (ref "U5") (pin "3") (pinfunction "VBB1_3") (pintype "power_in"))
      (node (ref "U6") (pin "22") (pinfunction "VBB_22") (pintype "power_in"))
      (node (ref "U6") (pin "3") (pinfunction "VBB1_3") (pintype "power_in"))
      (node (ref "U7") (pin "22") (pinfunction "VBB_22") (pintype "power_in"))
      (node (ref "U7") (pin "3") (pinfunction "VBB1_3") (pintype "power_in"))
      (node (ref "U8") (pin "22") (pinfunction "VBB_22") (pintype "power_in"))
      (node (ref "U8") (pin "3") (pinfunction "VBB1_3") (pintype "power_in"))
      (node (ref "U9") (pin "22") (pinfunction "VBB_22") (pintype "power_in"))
      (node (ref "U9") (pin "3") (pinfunction "VBB1_3") (pintype "power_in"))
      (node (ref "X30") (pin "2") (pinfunction "S_2") (pintype "passive"))
    )
    (net (code "2") (name "+12V2") (class "Default")
      (node (ref "C40") (pin "1") (pinfunction "1_1") (pintype "passive"))
      (node (ref "C45") (pin "1") (pinfunction "1_1") (pintype "passive"))
      (node (ref "C60") (pin "1") (pinfunction "1_1") (pintype "passive"))
      (node (ref "C65") (pin "+") (pinfunction "+_+") (pintype "passive"))
      (node (ref "D1") (pin "C") (pinfunction "C_C") (pintype "passive"))
      (node (ref "D3") (pin "C") (pinfunction "C_C") (pintype "passive"))
      (node (ref "D6") (pin "C") (pinfunction "C_C") (pintype "passive"))
      (node (ref "D8") (pin "C") (pinfunction "C_C") (pintype "passive"))
      (node (ref "F3") (pin "P$2") (pinfunction "P$2_P$2") (pintype "bidirectional"))
      (node (ref "R3") (pin "2") (pinfunction "2_2") (pintype "passive"))
      (node (ref "R40") (pin "2") (pinfunction "2_2") (pintype "passive"))
      (node (ref "R41") (pin "2") (pinfunction "2_2") (pintype "passive"))
      (node (ref "R50") (pin "2") (pinfunction "2_2") (pintype "passive"))
      (node (ref "R55") (pin "2") (pinfunction "2_2") (pintype "passive"))
      (node (ref "R69") (pin "2") (pinfunction "2_2") (pintype "passive"))
      (node (ref "R73") (pin "2") (pinfunction "2_2") (pintype "passive"))
      (node (ref "U3") (pin "7") (pinfunction "VIN_7") (pintype "power_in"))
      (node (ref "X11") (pin "2") (pinfunction "1_2") (pintype "passive"))
      (node (ref "X11") (pin "4") (pinfunction "1_4") (pintype "passive"))
      (node (ref "X11") (pin "6") (pinfunction "1_6") (pintype "passive"))
      (node (ref "X11") (pin "8") (pinfunction "1_8") (pintype "passive"))
      (node (ref "X35") (pin "2") (pinfunction "2_2") (pintype "passive"))
      (node (ref "X36") (pin "2") (pinfunction "2_2") (pintype "passive"))
      (node (ref "X37") (pin "2") (pinfunction "2_2") (pintype "passive"))
      (node (ref "X9") (pin "2") (pinfunction "S_2") (pintype "passive"))
    )
    (net (code "3") (name "+12V3") (class "Default")
      (node (ref "C54") (pin "1") (pinfunction "1_1") (pintype "passive"))
      (node (ref "C62") (pin "1") (pinfunction "1_1") (pintype "passive"))
      (node (ref "C66") (pin "+") (pinfunction "+_+") (pintype "passive"))
      (node (ref "D10") (pin "C") (pinfunction "C_C") (pintype "passive"))
      (node (ref "D7") (pin "C") (pinfunction "C_C") (pintype "passive"))
      (node (ref "F4") (pin "P$2") (pinfunction "2_P$2") (pintype "passive"))
      (node (ref "R58") (pin "2") (pinfunction "2_2") (pintype "passive"))
      (node (ref "X11") (pin "10") (pinfunction "1_10") (pintype "passive"))
      (node (ref "X38") (pin "2") (pinfunction "2_2") (pintype "passive"))
    )
    (net (code "4") (name "/AREF") (class "Default")
      (node (ref "C6") (pin "1") (pinfunction "1_1") (pintype "passive"))
      (node (ref "U2") (pin "98") (pinfunction "AREF_98") (pintype "bidirectional"))
    )
    (net (code "5") (name "/BED-HEAT") (class "Default")
      (node (ref "R56") (pin "1") (pinfunction "1_1") (pintype "passive"))
      (node (ref "R57") (pin "1") (pinfunction "1_1") (pintype "passive"))
      (node (ref "U2") (pin "7") (pinfunction "(OC3C/INT5)PE5_7") (pintype "bidirectional"))
    )
    (net (code "6") (name "/D+") (class "Default")
      (node (ref "R2") (pin "1") (pinfunction "1_1") (pintype "passive"))
      (node (ref "X2") (pin "3") (pinfunction "3_3") (pintype "bidirectional"))
      (node (ref "Z2") (pin "2") (pinfunction "2_2") (pintype "passive"))
    )
    (net (code "7") (name "/D-") (class "Default")
      (node (ref "R1") (pin "1") (pinfunction "1_1") (pintype "passive"))
      (node (ref "X2") (pin "2") (pinfunction "2_2") (pintype "bidirectional"))
      (node (ref "Z1") (pin "2") (pinfunction "2_2") (pintype "passive"))
    )
    (net (code "8") (name "/DP-SS") (class "Default")
      (node (ref "U2") (pin "50") (pinfunction "(T0)PD7_50") (pintype "bidirectional"))
      (node (ref "U4") (pin "P05") (pinfunction "_CS_P05") (pintype "bidirectional"))
    )
    (net (code "9") (name "/DTR") (class "Default")
      (node (ref "JP2") (pin "1") (pinfunction "1_1") (pintype "passive"))
      (node (ref "JP2") (pin "2") (pinfunction "2_2") (pintype "passive"))
      (node (ref "RN5") (pin "5") (pinfunction "2_5") (pintype "passive"))
      (node (ref "U1") (pin "13") (pinfunction "(CTS/HWB/AIN6/TO/INT7)PD7_13") (pintype "bidirectional"))
      (node (ref "U10") (pin "3") (pinfunction "VIA_3") (pintype "bidirectional"))
    )
    (net (code "10") (name "/E0-DIR") (class "Default")
      (node (ref "TP11") (pin "TP") (pinfunction "TP_TP") (pintype "input"))
      (node (ref "U2") (pin "41") (pinfunction "PL6_41") (pintype "bidirectional"))
      (node (ref "U8") (pin "20") (pinfunction "DIR_20") (pintype "input"))
    )
    (net (code "11") (name "/E0-EN") (class "Default")
      (node (ref "R62") (pin "2") (pinfunction "2_2") (pintype "passive"))
      (node (ref "TP14") (pin "TP") (pinfunction "TP_TP") (pintype "input"))
      (node (ref "U2") (pin "74") (pinfunction "(AD4)PA4_74") (pintype "bidirectional"))
      (node (ref "U8") (pin "5") (pinfunction "EN_5") (pintype "input"))
    )
    (net (code "12") (name "/E0-MS1") (class "Default")
      (node (ref "U2") (pin "86") (pinfunction "PK3(ADC11/PCINT19)_86") (pintype "bidirectional"))
      (node (ref "U8") (pin "11") (pinfunction "MS1_11") (pintype "input"))
    )
    (net (code "13") (name "/E0-MS2") (class "Default")
      (node (ref "U2") (pin "85") (pinfunction "PK4(ADC12/PCINT20)_85") (pintype "bidirectional"))
      (node (ref "U8") (pin "12") (pinfunction "MS2_12") (pintype "input"))
    )
    (net (code "14") (name "/E0-REF") (class "Default")
      (node (ref "TP12") (pin "TP") (pinfunction "TP_TP") (pintype "input"))
      (node (ref "U4") (pin "P17") (pinfunction "W1_P17") (pintype "bidirectional"))
      (node (ref "U8") (pin "18") (pinfunction "REF_18") (pintype "input"))
    )
    (net (code "15") (name "/E0-STEP") (class "Default")
      (node (ref "TP13") (pin "TP") (pinfunction "TP_TP") (pintype "input"))
      (node (ref "U2") (pin "56") (pinfunction "(A11)PC3_56") (pintype "bidirectional"))
      (node (ref "U8") (pin "17") (pinfunction "STEP_17") (pintype "input"))
    )
    (net (code "16") (name "/E1-DIR") (class "Default")
      (node (ref "TP15") (pin "TP") (pinfunction "TP_TP") (pintype "input"))
      (node (ref "U2") (pin "42") (pinfunction "PL7_42") (pintype "bidirectional"))
      (node (ref "U9") (pin "20") (pinfunction "DIR_20") (pintype "input"))
    )
    (net (code "17") (name "/E1-EN") (class "Default")
      (node (ref "R63") (pin "2") (pinfunction "2_2") (pintype "passive"))
      (node (ref "TP18") (pin "TP") (pinfunction "TP_TP") (pintype "input"))
      (node (ref "U2") (pin "75") (pinfunction "(AD3)PA3_75") (pintype "bidirectional"))
      (node (ref "U9") (pin "5") (pinfunction "EN_5") (pintype "input"))
    )
    (net (code "18") (name "/E1-MS1") (class "Default")
      (node (ref "U2") (pin "88") (pinfunction "PK1(ADC9/PCINT17)_88") (pintype "bidirectional"))
      (node (ref "U9") (pin "11") (pinfunction "MS1_11") (pintype "input"))
    )
    (net (code "19") (name "/E1-MS2") (class "Default")
      (node (ref "U2") (pin "87") (pinfunction "PK2(ADC10/PCINT18)_87") (pintype "bidirectional"))
      (node (ref "U9") (pin "12") (pinfunction "MS2_12") (pintype "input"))
    )
    (net (code "20") (name "/E1-REF") (class "Default")
      (node (ref "TP17") (pin "TP") (pinfunction "TP_TP") (pintype "input"))
      (node (ref "U4") (pin "P20") (pinfunction "W2_P20") (pintype "bidirectional"))
      (node (ref "U9") (pin "18") (pinfunction "REF_18") (pintype "input"))
    )
    (net (code "21") (name "/E1-STEP") (class "Default")
      (node (ref "TP16") (pin "TP") (pinfunction "TP_TP") (pintype "input"))
      (node (ref "U2") (pin "57") (pinfunction "(A12)PC4_57") (pintype "bidirectional"))
      (node (ref "U9") (pin "17") (pinfunction "STEP_17") (pintype "input"))
    )
    (net (code "22") (name "/FAN-0") (class "Default")
      (node (ref "R48") (pin "1") (pinfunction "1_1") (pintype "passive"))
      (node (ref "R49") (pin "1") (pinfunction "1_1") (pintype "passive"))
      (node (ref "U2") (pin "17") (pinfunction "PH5(OC4C)_17") (pintype "bidirectional"))
    )
    (net (code "23") (name "/FAN-1") (class "Default")
      (node (ref "R53") (pin "1") (pinfunction "1_1") (pintype "passive"))
      (node (ref "R54") (pin "1") (pinfunction "1_1") (pintype "passive"))
      (node (ref "U2") (pin "15") (pinfunction "PH3(OC4A)_15") (pintype "bidirectional"))
    )
    (net (code "24") (name "/FAN-2") (class "Default")
      (node (ref "R70") (pin "1") (pinfunction "1_1") (pintype "passive"))
      (node (ref "R71") (pin "1") (pinfunction "1_1") (pintype "passive"))
      (node (ref "U2") (pin "6") (pinfunction "(OC3B/INT4)PE4_6") (pintype "bidirectional"))
      (node (ref "X34") (pin "4") (pinfunction "4_4") (pintype "passive"))
    )
    (net (code "25") (name "/HEAT-0") (class "Default")
      (node (ref "R42") (pin "1") (pinfunction "1_1") (pintype "passive"))
      (node (ref "R43") (pin "1") (pinfunction "1_1") (pintype "passive"))
      (node (ref "U2") (pin "18") (pinfunction "PH6(OC2B)_18") (pintype "bidirectional"))
    )
    (net (code "26") (name "/HEAT-1") (class "Default")
      (node (ref "R51") (pin "1") (pinfunction "1_1") (pintype "passive"))
      (node (ref "R52") (pin "1") (pinfunction "1_1") (pintype "passive"))
      (node (ref "U2") (pin "16") (pinfunction "PH4(OC4B)_16") (pintype "bidirectional"))
    )
    (net (code "27") (name "/L13") (class "Default")
      (node (ref "R33") (pin "1") (pinfunction "1_1") (pintype "passive"))
      (node (ref "U2") (pin "26") (pinfunction "(OC0A/OC1C/PCINT7)PB7_26") (pintype "bidirectional"))
      (node (ref "X34") (pin "3") (pinfunction "3_3") (pintype "passive"))
    )
    (net (code "28") (name "/MISO2") (class "Default")
      (node (ref "U1") (pin "17") (pinfunction "(PD0/MISO/PCINT3)PB3_17") (pintype "bidirectional"))
      (node (ref "X17") (pin "1") (pinfunction "1_1") (pintype "passive"))
    )
    (net (code "29") (name "/MOSI2") (class "Default")
      (node (ref "U1") (pin "16") (pinfunction "(PDI/MOSI/PCINT2)PB2_16") (pintype "bidirectional"))
      (node (ref "X17") (pin "4") (pinfunction "4_4") (pintype "passive"))
    )
    (net (code "30") (name "/N$96") (class "Default")
      (node (ref "U4") (pin "P14") (pinfunction "W3_P14") (pintype "bidirectional"))
    )
    (net (code "31") (name "/OVREF") (class "Default")
      (node (ref "D11") (pin "C") (pinfunction "C_C") (pintype "passive"))
      (node (ref "D12") (pin "C") (pinfunction "C_C") (pintype "passive"))
      (node (ref "D14") (pin "C") (pinfunction "C_C") (pintype "passive"))
      (node (ref "D16") (pin "C") (pinfunction "C_C") (pintype "passive"))
      (node (ref "D18") (pin "C") (pinfunction "C_C") (pintype "passive"))
      (node (ref "R73") (pin "1") (pinfunction "1_1") (pintype "passive"))
    )
    (net (code "32") (name "/PA0") (class "Default")
      (node (ref "U2") (pin "78") (pinfunction "(AD0)PA0_78") (pintype "bidirectional"))
      (node (ref "X20") (pin "3") (pinfunction "3_3") (pintype "passive"))
    )
    (net (code "33") (name "/PA1") (class "Default")
      (node (ref "U2") (pin "77") (pinfunction "(AD1)PA1_77") (pintype "bidirectional"))
      (node (ref "X25") (pin "1") (pinfunction "S_1") (pintype "passive"))
      (node (ref "X31") (pin "3") (pinfunction "3_3") (pintype "passive"))
    )
    (net (code "34") (name "/PA2") (class "Default")
      (node (ref "U2") (pin "76") (pinfunction "(AD2)PA2_76") (pintype "bidirectional"))
      (node (ref "X26") (pin "1") (pinfunction "S_1") (pintype "passive"))
      (node (ref "X32") (pin "3") (pinfunction "3_3") (pintype "passive"))
    )
    (net (code "35") (name "/PB0_SS") (class "Default")
      (node (ref "U2") (pin "19") (pinfunction "(SS/PCINT0)PB0_19") (pintype "bidirectional"))
      (node (ref "X12") (pin "6") (pinfunction "6_6") (pintype "passive"))
    )
    (net (code "36") (name "/PB1_SCK") (class "Default")
      (node (ref "U2") (pin "20") (pinfunction "(SCK/PCINT1)PB1_20") (pintype "bidirectional"))
      (node (ref "U4") (pin "P08") (pinfunction "SCK_P08") (pintype "bidirectional"))
      (node (ref "X12") (pin "5") (pinfunction "5_5") (pintype "passive"))
      (node (ref "X18") (pin "3") (pinfunction "3_3") (pintype "passive"))
    )
    (net (code "37") (name "/PB2_MOSI") (class "Default")
      (node (ref "U2") (pin "21") (pinfunction "(MOSI/PCINT2)PB2_21") (pintype "bidirectional"))
      (node (ref "U4") (pin "P07") (pinfunction "SDI_P07") (pintype "bidirectional"))
      (node (ref "X12") (pin "4") (pinfunction "4_4") (pintype "passive"))
      (node (ref "X18") (pin "4") (pinfunction "4_4") (pintype "passive"))
    )
    (net (code "38") (name "/PB3_MISO") (class "Default")
      (node (ref "U2") (pin "22") (pinfunction "(MISO/PCINT3)PB3_22") (pintype "bidirectional"))
      (node (ref "X12") (pin "3") (pinfunction "3_3") (pintype "passive"))
      (node (ref "X18") (pin "1") (pinfunction "1_1") (pintype "passive"))
    )
    (net (code "39") (name "/PC5") (class "Default")
      (node (ref "U2") (pin "58") (pinfunction "(A13)PC5_58") (pintype "bidirectional"))
      (node (ref "X20") (pin "4") (pinfunction "4_4") (pintype "passive"))
    )
    (net (code "40") (name "/PC6") (class "Default")
      (node (ref "U2") (pin "59") (pinfunction "(A14)PC6_59") (pintype "bidirectional"))
      (node (ref "X31") (pin "4") (pinfunction "4_4") (pintype "passive"))
    )
    (net (code "41") (name "/PC7") (class "Default")
      (node (ref "U2") (pin "60") (pinfunction "(A15)PC7_60") (pintype "bidirectional"))
      (node (ref "X24") (pin "1") (pinfunction "S_1") (pintype "passive"))
      (node (ref "X32") (pin "4") (pinfunction "4_4") (pintype "passive"))
    )
    (net (code "42") (name "/PD4") (class "Default")
      (node (ref "U2") (pin "47") (pinfunction "(ICP1)PD4_47") (pintype "bidirectional"))
      (node (ref "X13") (pin "14") (pinfunction "14_14") (pintype "passive"))
    )
    (net (code "43") (name "/PD5") (class "Default")
      (node (ref "U2") (pin "48") (pinfunction "(XCK1)PD5_48") (pintype "bidirectional"))
      (node (ref "X13") (pin "12") (pinfunction "12_12") (pintype "passive"))
    )
    (net (code "44") (name "/PD6") (class "Default")
      (node (ref "U2") (pin "49") (pinfunction "(T1)PD6_49") (pintype "bidirectional"))
      (node (ref "X13") (pin "10") (pinfunction "10_10") (pintype "passive"))
    )
    (net (code "45") (name "/PE2") (class "Default")
      (node (ref "U2") (pin "4") (pinfunction "(XCK0/AIN0)PE2_4") (pintype "bidirectional"))
      (node (ref "X13") (pin "20") (pinfunction "20_20") (pintype "passive"))
    )
    (net (code "46") (name "/PE3") (class "Default")
      (node (ref "U2") (pin "5") (pinfunction "(OC3A/AIN1)PE3_5") (pintype "bidirectional"))
      (node (ref "X34") (pin "5") (pinfunction "5_5") (pintype "passive"))
    )
    (net (code "47") (name "/PE6") (class "Default")
      (node (ref "U2") (pin "8") (pinfunction "(T3/INT6)PE6_8") (pintype "bidirectional"))
      (node (ref "X13") (pin "18") (pinfunction "18_18") (pintype "passive"))
    )
    (net (code "48") (name "/PE7") (class "Default")
      (node (ref "U2") (pin "9") (pinfunction "(CLKO/ICP3/INT7)PE7_9") (pintype "bidirectional"))
      (node (ref "X13") (pin "16") (pinfunction "16_16") (pintype "passive"))
    )
    (net (code "49") (name "/PF3") (class "Default")
      (node (ref "U2") (pin "94") (pinfunction "(ADC3)PF3_94") (pintype "bidirectional"))
      (node (ref "X40") (pin "4") (pinfunction "4_4") (pintype "passive"))
    )
    (net (code "50") (name "/PF4") (class "Default")
      (node (ref "U2") (pin "93") (pinfunction "(ADC4/TCK)PF4_93") (pintype "bidirectional"))
      (node (ref "X40") (pin "6") (pinfunction "6_6") (pintype "passive"))
    )
    (net (code "51") (name "/PF5") (class "Default")
      (node (ref "U2") (pin "92") (pinfunction "(ADC5/TMS)PF5_92") (pintype "bidirectional"))
      (node (ref "X40") (pin "8") (pinfunction "8_8") (pintype "passive"))
    )
    (net (code "52") (name "/PF6") (class "Default")
      (node (ref "U2") (pin "91") (pinfunction "(ADC6/TDO)PF6_91") (pintype "bidirectional"))
      (node (ref "X40") (pin "3") (pinfunction "3_3") (pintype "passive"))
    )
    (net (code "53") (name "/PG3") (class "Default")
      (node (ref "U2") (pin "28") (pinfunction "(TOSC2)PG3_28") (pintype "bidirectional"))
      (node (ref "X13") (pin "7") (pinfunction "7_7") (pintype "passive"))
    )
    (net (code "54") (name "/PG4") (class "Default")
      (node (ref "U2") (pin "29") (pinfunction "(TOSC1)PG4_29") (pintype "bidirectional"))
      (node (ref "X13") (pin "5") (pinfunction "5_5") (pintype "passive"))
    )
    (net (code "55") (name "/PG5") (class "Default")
      (node (ref "U2") (pin "1") (pinfunction "(OC0B)PG5_1") (pintype "bidirectional"))
      (node (ref "X34") (pin "6") (pinfunction "6_6") (pintype "passive"))
      (node (ref "X5") (pin "1") (pinfunction "S_1") (pintype "passive"))
    )
    (net (code "56") (name "/PH2") (class "Default")
      (node (ref "U2") (pin "14") (pinfunction "PH2(XCK2)_14") (pintype "bidirectional"))
      (node (ref "X13") (pin "8") (pinfunction "8_8") (pintype "passive"))
    )
    (net (code "57") (name "/PH7") (class "Default")
      (node (ref "U2") (pin "27") (pinfunction "PH7(T4)_27") (pintype "bidirectional"))
      (node (ref "X13") (pin "6") (pinfunction "6_6") (pintype "passive"))
    )
    (net (code "58") (name "/PJ2") (class "Default")
      (node (ref "U2") (pin "65") (pinfunction "PJ2(XCK3/PCINT11)_65") (pintype "bidirectional"))
      (node (ref "X13") (pin "9") (pinfunction "9_9") (pintype "passive"))
    )
    (net (code "59") (name "/PJ3") (class "Default")
      (node (ref "U2") (pin "66") (pinfunction "PJ3(PCINT12)_66") (pintype "bidirectional"))
      (node (ref "X13") (pin "11") (pinfunction "11_11") (pintype "passive"))
    )
    (net (code "60") (name "/PJ4") (class "Default")
      (node (ref "U2") (pin "67") (pinfunction "PJ4(PCINT13)_67") (pintype "bidirectional"))
      (node (ref "X13") (pin "15") (pinfunction "15_15") (pintype "passive"))
    )
    (net (code "61") (name "/PJ5") (class "Default")
      (node (ref "U2") (pin "68") (pinfunction "PJ5(PCINT14)_68") (pintype "bidirectional"))
      (node (ref "X13") (pin "17") (pinfunction "17_17") (pintype "passive"))
    )
    (net (code "62") (name "/PJ6") (class "Default")
      (node (ref "U2") (pin "69") (pinfunction "PJ6(PCINT15)_69") (pintype "bidirectional"))
      (node (ref "X13") (pin "19") (pinfunction "19_19") (pintype "passive"))
    )
    (net (code "63") (name "/PJ7") (class "Default")
      (node (ref "U2") (pin "79") (pinfunction "PJ7_79") (pintype "bidirectional"))
      (node (ref "X13") (pin "13") (pinfunction "13_13") (pintype "passive"))
    )
    (net (code "64") (name "/PK0") (class "Default")
      (node (ref "U2") (pin "89") (pinfunction "PK0(ADC8/PCINT16)_89") (pintype "bidirectional"))
      (node (ref "X40") (pin "7") (pinfunction "7_7") (pintype "passive"))
    )
    (net (code "65") (name "/PL3") (class "Default")
      (node (ref "U2") (pin "38") (pinfunction "PL3(OC5A)_38") (pintype "bidirectional"))
      (node (ref "X12") (pin "2") (pinfunction "2_2") (pintype "passive"))
      (node (ref "X32") (pin "5") (pinfunction "5_5") (pintype "passive"))
    )
    (net (code "66") (name "/PL4") (class "Default")
      (node (ref "U2") (pin "39") (pinfunction "PL4(OC5B)_39") (pintype "bidirectional"))
      (node (ref "X31") (pin "5") (pinfunction "5_5") (pintype "passive"))
    )
    (net (code "67") (name "/PL5") (class "Default")
      (node (ref "U2") (pin "40") (pinfunction "PL5(OC5C)_40") (pintype "bidirectional"))
      (node (ref "X20") (pin "5") (pinfunction "5_5") (pintype "passive"))
    )
    (net (code "68") (name "/RD+") (class "Default")
      (node (ref "R2") (pin "2") (pinfunction "2_2") (pintype "passive"))
      (node (ref "U1") (pin "29") (pinfunction "D+_29") (pintype "bidirectional"))
    )
    (net (code "69") (name "/RD-") (class "Default")
      (node (ref "R1") (pin "2") (pinfunction "2_2") (pintype "passive"))
      (node (ref "U1") (pin "30") (pinfunction "D-_30") (pintype "bidirectional"))
    )
    (net (code "70") (name "/RESET") (class "Default")
      (node (ref "C1") (pin "1") (pinfunction "1_1") (pintype "passive"))
      (node (ref "C10") (pin "2") (pinfunction "2_2") (pintype "passive"))
      (node (ref "D5") (pin "A") (pinfunction "A_A") (pintype "passive"))
      (node (ref "R46") (pin "1") (pinfunction "1_1") (pintype "passive"))
      (node (ref "S1") (pin "1") (pinfunction "P_1") (pintype "passive"))
      (node (ref "U2") (pin "30") (pinfunction "RESET_30") (pintype "input"))
      (node (ref "X18") (pin "5") (pinfunction "5_5") (pintype "passive"))
    )
    (net (code "71") (name "/RESET2") (class "Default")
      (node (ref "D4") (pin "A") (pinfunction "A_A") (pintype "passive"))
      (node (ref "R47") (pin "1") (pinfunction "1_1") (pintype "passive"))
      (node (ref "U1") (pin "24") (pinfunction "RESET(PC1/DW)_24") (pintype "input"))
      (node (ref "X17") (pin "5") (pinfunction "5_5") (pintype "passive"))
    )
    (net (code "72") (name "/RST-IO") (class "Default")
      (node (ref "C10") (pin "1") (pinfunction "1_1") (pintype "passive"))
      (node (ref "U10") (pin "14") (pinfunction "VOA_14") (pintype "bidirectional"))
    )
    (net (code "73") (name "/RX0") (class "Default")
      (node (ref "R34") (pin "2") (pinfunction "2_2") (pintype "passive"))
      (node (ref "U2") (pin "2") (pinfunction "(RXD0/PCIN8)PE0_2") (pintype "bidirectional"))
      (node (ref "X39") (pin "3") (pinfunction "3_3") (pintype "passive"))
    )
    (net (code "74") (name "/RX0-I") (class "Default")
      (node (ref "U1") (pin "9") (pinfunction "(TXD1/INT3)PD3_9") (pintype "bidirectional"))
      (node (ref "U10") (pin "5") (pinfunction "VIC_5") (pintype "bidirectional"))
    )
    (net (code "75") (name "/RX1") (class "Default")
      (node (ref "U2") (pin "45") (pinfunction "(RXD1/INT2)PD2_45") (pintype "bidirectional"))
      (node (ref "X39") (pin "5") (pinfunction "5_5") (pintype "passive"))
    )
    (net (code "76") (name "/RX2") (class "Default")
      (node (ref "U2") (pin "12") (pinfunction "PH0(RXD2)_12") (pintype "bidirectional"))
      (node (ref "X39") (pin "7") (pinfunction "7_7") (pintype "passive"))
    )
    (net (code "77") (name "/RX3") (class "Default")
      (node (ref "U2") (pin "63") (pinfunction "PJ0(RXD3/PCINT9)_63") (pintype "bidirectional"))
      (node (ref "X39") (pin "9") (pinfunction "9_9") (pintype "passive"))
    )
    (net (code "78") (name "/RXL") (class "Default")
      (node (ref "LED10") (pin "C") (pinfunction "C_C") (pintype "passive"))
      (node (ref "U1") (pin "10") (pinfunction "(INT5/AIN3)PD4_10") (pintype "bidirectional"))
    )
    (net (code "79") (name "/SCK2") (class "Default")
      (node (ref "U1") (pin "15") (pinfunction "(SCLK/PCINT1)PB1_15") (pintype "bidirectional"))
      (node (ref "X17") (pin "3") (pinfunction "3_3") (pintype "passive"))
    )
    (net (code "80") (name "/SCL") (class "Default")
      (node (ref "R45") (pin "1") (pinfunction "1_1") (pintype "passive"))
      (node (ref "U2") (pin "43") (pinfunction "(SCL/INT0)PD0_43") (pintype "bidirectional"))
      (node (ref "X10") (pin "4") (pinfunction "S_4") (pintype "passive"))
    )
    (net (code "81") (name "/SDA") (class "Default")
      (node (ref "R44") (pin "1") (pinfunction "1_1") (pintype "passive"))
      (node (ref "U2") (pin "44") (pinfunction "(SDA/INT1)PD1_44") (pintype "bidirectional"))
      (node (ref "X10") (pin "3") (pinfunction "S_3") (pintype "passive"))
    )
    (net (code "82") (name "/THERM0") (class "Default")
      (node (ref "C59") (pin "1") (pinfunction "1_1") (pintype "passive"))
      (node (ref "D11") (pin "A") (pinfunction "A_A") (pintype "passive"))
      (node (ref "D13") (pin "C") (pinfunction "C_C") (pintype "passive"))
      (node (ref "R32") (pin "1") (pinfunction "1_1") (pintype "passive"))
      (node (ref "TP20") (pin "TP") (pinfunction "TP_TP") (pintype "input"))
      (node (ref "U2") (pin "97") (pinfunction "(ADC0)PF0_97") (pintype "bidirectional"))
    )
    (net (code "83") (name "/THERM1") (class "Default")
      (node (ref "C56") (pin "1") (pinfunction "1_1") (pintype "passive"))
      (node (ref "D14") (pin "A") (pinfunction "A_A") (pintype "passive"))
      (node (ref "D15") (pin "C") (pinfunction "C_C") (pintype "passive"))
      (node (ref "R37") (pin "1") (pinfunction "1_1") (pintype "passive"))
      (node (ref "TP21") (pin "TP") (pinfunction "TP_TP") (pintype "input"))
      (node (ref "U2") (pin "96") (pinfunction "(ADC1)PF1_96") (pintype "bidirectional"))
    )
    (net (code "84") (name "/THERM2") (class "Default")
      (node (ref "C64") (pin "1") (pinfunction "1_1") (pintype "passive"))
      (node (ref "D16") (pin "A") (pinfunction "A_A") (pintype "passive"))
      (node (ref "D17") (pin "C") (pinfunction "C_C") (pintype "passive"))
      (node (ref "R28") (pin "1") (pinfunction "1_1") (pintype "passive"))
      (node (ref "TP22") (pin "TP") (pinfunction "TP_TP") (pintype "input"))
      (node (ref "U2") (pin "95") (pinfunction "(ADC2)PF2_95") (pintype "bidirectional"))
    )
    (net (code "85") (name "/THERM3") (class "Default")
      (node (ref "C3") (pin "1") (pinfunction "1_1") (pintype "passive"))
      (node (ref "D18") (pin "A") (pinfunction "A_A") (pintype "passive"))
      (node (ref "D19") (pin "C") (pinfunction "C_C") (pintype "passive"))
      (node (ref "R39") (pin "1") (pinfunction "1_1") (pintype "passive"))
      (node (ref "TP23") (pin "TP") (pinfunction "TP_TP") (pintype "input"))
      (node (ref "U2") (pin "90") (pinfunction "(ADC7/TDI)PF7_90") (pintype "bidirectional"))
      (node (ref "X40") (pin "5") (pinfunction "5_5") (pintype "passive"))
    )
    (net (code "86") (name "/TX0") (class "Default")
      (node (ref "U10") (pin "11") (pinfunction "VID_11") (pintype "bidirectional"))
      (node (ref "U2") (pin "3") (pinfunction "(TXD0)PE1_3") (pintype "bidirectional"))
      (node (ref "X39") (pin "4") (pinfunction "4_4") (pintype "passive"))
    )
    (net (code "87") (name "/TX0-I") (class "Default")
      (node (ref "U1") (pin "8") (pinfunction "(RXD1/AIN1/INT2)PD2_8") (pintype "bidirectional"))
      (node (ref "U10") (pin "6") (pinfunction "VOD_6") (pintype "bidirectional"))
    )
    (net (code "88") (name "/TX1") (class "Default")
      (node (ref "U2") (pin "46") (pinfunction "(TXD1/INT3)PD3_46") (pintype "bidirectional"))
      (node (ref "X39") (pin "6") (pinfunction "6_6") (pintype "passive"))
    )
    (net (code "89") (name "/TX2") (class "Default")
      (node (ref "U2") (pin "13") (pinfunction "PH1(TXD2)_13") (pintype "bidirectional"))
      (node (ref "X39") (pin "8") (pinfunction "8_8") (pintype "passive"))
    )
    (net (code "90") (name "/TX3") (class "Default")
      (node (ref "U2") (pin "64") (pinfunction "PJ1(TXD3/PCINT10)_64") (pintype "bidirectional"))
      (node (ref "X39") (pin "10") (pinfunction "10_10") (pintype "passive"))
    )
    (net (code "91") (name "/TXL") (class "Default")
      (node (ref "LED9") (pin "C") (pinfunction "C_C") (pintype "passive"))
      (node (ref "U1") (pin "11") (pinfunction "(XCK/AIN4/PCINT12)PD5_11") (pintype "bidirectional"))
    )
    (net (code "92") (name "/U1-PB0") (class "Default")
      (node (ref "U1") (pin "14") (pinfunction "(SS/PCINT0)PB0_14") (pintype "bidirectional"))
      (node (ref "X16") (pin "7") (pinfunction "7_7") (pintype "passive"))
    )
    (net (code "93") (name "/U1-PB4") (class "Default")
      (node (ref "U1") (pin "18") (pinfunction "(T1/PCINT4)PB4_18") (pintype "bidirectional"))
      (node (ref "X16") (pin "9") (pinfunction "9_9") (pintype "passive"))
    )
    (net (code "94") (name "/U1-PB5") (class "Default")
      (node (ref "U1") (pin "19") (pinfunction "(PCINT5)PB5_19") (pintype "bidirectional"))
      (node (ref "X16") (pin "12") (pinfunction "12_12") (pintype "passive"))
    )
    (net (code "95") (name "/U1-PB6") (class "Default")
      (node (ref "U1") (pin "20") (pinfunction "(PCINT6)PB6_20") (pintype "bidirectional"))
      (node (ref "X16") (pin "11") (pinfunction "11_11") (pintype "passive"))
    )
    (net (code "96") (name "/U1-PB7") (class "Default")
      (node (ref "U1") (pin "21") (pinfunction "(PCINT7/OC0A/OC1C)PB7_21") (pintype "bidirectional"))
      (node (ref "X16") (pin "14") (pinfunction "14_14") (pintype "passive"))
    )
    (net (code "97") (name "/U1-PC2") (class "Default")
      (node (ref "U1") (pin "5") (pinfunction "(AIN2/PCINT11)PC2_5") (pintype "bidirectional"))
      (node (ref "X16") (pin "5") (pinfunction "5_5") (pintype "passive"))
    )
    (net (code "98") (name "/U1-PC4") (class "Default")
      (node (ref "U1") (pin "26") (pinfunction "(PCINT10)PC4_26") (pintype "bidirectional"))
    )
    (net (code "99") (name "/U1-PC5") (class "Default")
      (node (ref "U1") (pin "25") (pinfunction "(PCINT9/OC1B)PC5_25") (pintype "bidirectional"))
      (node (ref "X16") (pin "15") (pinfunction "15_15") (pintype "passive"))
    )
    (net (code "100") (name "/U1-PC6") (class "Default")
      (node (ref "U1") (pin "23") (pinfunction "(OC1A/PCINT8)PC6_23") (pintype "bidirectional"))
      (node (ref "X16") (pin "16") (pinfunction "16_16") (pintype "passive"))
    )
    (net (code "101") (name "/U1-PC7") (class "Default")
      (node (ref "U1") (pin "22") (pinfunction "(INT4/ICP1/CLK0)PC7_22") (pintype "bidirectional"))
      (node (ref "X16") (pin "13") (pinfunction "13_13") (pintype "passive"))
    )
    (net (code "102") (name "/U1-PD0") (class "Default")
      (node (ref "U1") (pin "6") (pinfunction "(OC0B/INT0)PD0_6") (pintype "bidirectional"))
      (node (ref "X16") (pin "10") (pinfunction "10_10") (pintype "passive"))
    )
    (net (code "103") (name "/U1-PD1") (class "Default")
      (node (ref "U1") (pin "7") (pinfunction "(AIN0/INT1)PD1_7") (pintype "bidirectional"))
      (node (ref "X16") (pin "8") (pinfunction "8_8") (pintype "passive"))
    )
    (net (code "104") (name "/U1-PD6") (class "Default")
      (node (ref "U1") (pin "12") (pinfunction "(RTS/AIN5/INT6)PD6_12") (pintype "bidirectional"))
      (node (ref "X16") (pin "6") (pinfunction "6_6") (pintype "passive"))
    )
    (net (code "105") (name "/USBVCC") (class "Default")
      (node (ref "C11") (pin "1") (pinfunction "1_1") (pintype "passive"))
      (node (ref "C14") (pin "1") (pinfunction "1_1") (pintype "passive"))
      (node (ref "C15") (pin "1") (pinfunction "1_1") (pintype "passive"))
      (node (ref "C2") (pin "2") (pinfunction "2_2") (pintype "passive"))
      (node (ref "C67") (pin "2") (pinfunction "2_2") (pintype "passive"))
      (node (ref "C70") (pin "1") (pinfunction "1_1") (pintype "passive"))
      (node (ref "D4") (pin "C") (pinfunction "C_C") (pintype "passive"))
      (node (ref "F1") (pin "1") (pinfunction "1_1") (pintype "passive"))
      (node (ref "R47") (pin "2") (pinfunction "2_2") (pintype "passive"))
      (node (ref "RN5") (pin "2") (pinfunction "1_2") (pintype "passive"))
      (node (ref "RN5") (pin "3") (pinfunction "1_3") (pintype "passive"))
      (node (ref "RN5") (pin "4") (pinfunction "1_4") (pintype "passive"))
      (node (ref "U1") (pin "31") (pinfunction "UVCC_31") (pintype "power_in"))
      (node (ref "U1") (pin "32") (pinfunction "AVCC_32") (pintype "power_in"))
      (node (ref "U1") (pin "4") (pinfunction "VCC_4") (pintype "power_in"))
      (node (ref "U10") (pin "1") (pinfunction "VDD1A_1") (pintype "bidirectional"))
      (node (ref "U10") (pin "7") (pinfunction "VDD1B_7") (pintype "bidirectional"))
      (node (ref "X16") (pin "1") (pinfunction "1_1") (pintype "passive"))
      (node (ref "X16") (pin "2") (pinfunction "2_2") (pintype "passive"))
      (node (ref "X17") (pin "2") (pinfunction "2_2") (pintype "passive"))
    )
    (net (code "106") (name "/USHIELD") (class "Default")
      (node (ref "C63") (pin "1") (pinfunction "1_1") (pintype "passive"))
      (node (ref "R72") (pin "2") (pinfunction "2_2") (pintype "passive"))
      (node (ref "X2") (pin "P$1") (pinfunction "P$1_P$1") (pintype "bidirectional"))
      (node (ref "X2") (pin "P$2") (pinfunction "P$2_P$2") (pintype "bidirectional"))
      (node (ref "Z1") (pin "1") (pinfunction "1_1") (pintype "passive"))
      (node (ref "Z2") (pin "1") (pinfunction "1_1") (pintype "passive"))
    )
    (net (code "107") (name "/VUCAP") (class "Default")
      (node (ref "C16") (pin "1") (pinfunction "1_1") (pintype "passive"))
      (node (ref "U1") (pin "27") (pinfunction "UCAP_27") (pintype "passive"))
    )
    (net (code "108") (name "/X-DIR") (class "Default")
      (node (ref "TP1") (pin "TP") (pinfunction "TP_TP") (pintype "input"))
      (node (ref "U2") (pin "36") (pinfunction "PL1(ICP5)_36") (pintype "bidirectional"))
      (node (ref "U5") (pin "20") (pinfunction "DIR_20") (pintype "input"))
    )
    (net (code "109") (name "/X-EN") (class "Default")
      (node (ref "R60") (pin "2") (pinfunction "2_2") (pintype "passive"))
      (node (ref "TP4") (pin "TP") (pinfunction "TP_TP") (pintype "input"))
      (node (ref "U2") (pin "71") (pinfunction "(AD7)PA7_71") (pintype "bidirectional"))
      (node (ref "U5") (pin "5") (pinfunction "EN_5") (pintype "input"))
    )
    (net (code "110") (name "/X-MIN") (class "Default")
      (node (ref "U2") (pin "25") (pinfunction "(OC1B/PCINT6)PB6_25") (pintype "bidirectional"))
      (node (ref "X23") (pin "1") (pinfunction "S_1") (pintype "passive"))
    )
    (net (code "111") (name "/X-MS1") (class "Default")
      (node (ref "U2") (pin "52") (pinfunction "(RD)PG1_52") (pintype "bidirectional"))
      (node (ref "U5") (pin "11") (pinfunction "MS1_11") (pintype "input"))
    )
    (net (code "112") (name "/X-MS2") (class "Default")
      (node (ref "U2") (pin "51") (pinfunction "(WR)PG0_51") (pintype "bidirectional"))
      (node (ref "U5") (pin "12") (pinfunction "MS2_12") (pintype "input"))
    )
    (net (code "113") (name "/X-REF") (class "Default")
      (node (ref "TP3") (pin "TP") (pinfunction "TP_TP") (pintype "input"))
      (node (ref "U4") (pin "P11") (pinfunction "W5_P11") (pintype "bidirectional"))
      (node (ref "U5") (pin "18") (pinfunction "REF_18") (pintype "input"))
    )
    (net (code "114") (name "/X-STEP") (class "Default")
      (node (ref "TP2") (pin "TP") (pinfunction "TP_TP") (pintype "input"))
      (node (ref "U2") (pin "53") (pinfunction "(A8)PC0_53") (pintype "bidirectional"))
      (node (ref "U5") (pin "17") (pinfunction "STEP_17") (pintype "input"))
    )
    (net (code "115") (name "/XVCC") (class "Default")
      (node (ref "F1") (pin "2") (pinfunction "2_2") (pintype "passive"))
      (node (ref "X2") (pin "1") (pinfunction "1_1") (pintype "bidirectional"))
    )
    (net (code "116") (name "/Y-DIR") (class "Default")
      (node (ref "TP0") (pin "TP") (pinfunction "TP_TP") (pintype "input"))
      (node (ref "U2") (pin "35") (pinfunction "PL0(ICP4)_35") (pintype "bidirectional"))
      (node (ref "U6") (pin "20") (pinfunction "DIR_20") (pintype "input"))
    )
    (net (code "117") (name "/Y-EN") (class "Default")
      (node (ref "R59") (pin "2") (pinfunction "2_2") (pintype "passive"))
      (node (ref "TP7") (pin "TP") (pinfunction "TP_TP") (pintype "input"))
      (node (ref "U2") (pin "72") (pinfunction "(AD6)PA6_72") (pintype "bidirectional"))
      (node (ref "U6") (pin "5") (pinfunction "EN_5") (pintype "input"))
    )
    (net (code "118") (name "/Y-MIN") (class "Default")
      (node (ref "U2") (pin "24") (pinfunction "(OC1A/PCINT5)PB5_24") (pintype "bidirectional"))
      (node (ref "X22") (pin "1") (pinfunction "S_1") (pintype "passive"))
    )
    (net (code "119") (name "/Y-MS1") (class "Default")
      (node (ref "U2") (pin "82") (pinfunction "PK7(ADC15/PCINT23)_82") (pintype "bidirectional"))
      (node (ref "U6") (pin "11") (pinfunction "MS1_11") (pintype "input"))
    )
    (net (code "120") (name "/Y-MS2") (class "Default")
      (node (ref "U2") (pin "70") (pinfunction "(ALE)PG2_70") (pintype "bidirectional"))
      (node (ref "U6") (pin "12") (pinfunction "MS2_12") (pintype "input"))
    )
    (net (code "121") (name "/Y-REF") (class "Default")
      (node (ref "TP6") (pin "TP") (pinfunction "TP_TP") (pintype "input"))
      (node (ref "U4") (pin "P02") (pinfunction "W6_P02") (pintype "bidirectional"))
      (node (ref "U6") (pin "18") (pinfunction "REF_18") (pintype "input"))
    )
    (net (code "122") (name "/Y-STEP") (class "Default")
      (node (ref "TP5") (pin "TP") (pinfunction "TP_TP") (pintype "input"))
      (node (ref "U2") (pin "54") (pinfunction "(A9)PC1_54") (pintype "bidirectional"))
      (node (ref "U6") (pin "17") (pinfunction "STEP_17") (pintype "input"))
    )
    (net (code "123") (name "/Z-DIR") (class "Default")
      (node (ref "TP19") (pin "TP") (pinfunction "TP_TP") (pintype "input"))
      (node (ref "U2") (pin "37") (pinfunction "PL2(T5)_37") (pintype "bidirectional"))
      (node (ref "U7") (pin "20") (pinfunction "DIR_20") (pintype "input"))
    )
    (net (code "124") (name "/Z-EN") (class "Default")
      (node (ref "R61") (pin "2") (pinfunction "2_2") (pintype "passive"))
      (node (ref "TP10") (pin "TP") (pinfunction "TP_TP") (pintype "input"))
      (node (ref "U2") (pin "73") (pinfunction "(AD5)PA5_73") (pintype "bidirectional"))
      (node (ref "U7") (pin "5") (pinfunction "EN_5") (pintype "input"))
    )
    (net (code "125") (name "/Z-MIN") (class "Default")
      (node (ref "U2") (pin "23") (pinfunction "(OC2A/PCINT4)PB4_23") (pintype "bidirectional"))
      (node (ref "X21") (pin "1") (pinfunction "S_1") (pintype "passive"))
    )
    (net (code "126") (name "/Z-MS1") (class "Default")
      (node (ref "U2") (pin "83") (pinfunction "PK6(ADC14/PCINT22)_83") (pintype "bidirectional"))
      (node (ref "U7") (pin "11") (pinfunction "MS1_11") (pintype "input"))
    )
    (net (code "127") (name "/Z-MS2") (class "Default")
      (node (ref "U2") (pin "84") (pinfunction "PK5(ADC13/PCINT21)_84") (pintype "bidirectional"))
      (node (ref "U7") (pin "12") (pinfunction "MS2_12") (pintype "input"))
    )
    (net (code "128") (name "/Z-REF") (class "Default")
      (node (ref "TP9") (pin "TP") (pinfunction "TP_TP") (pintype "input"))
      (node (ref "U4") (pin "P23") (pinfunction "W4_P23") (pintype "bidirectional"))
      (node (ref "U7") (pin "18") (pinfunction "REF_18") (pintype "input"))
    )
    (net (code "129") (name "/Z-STEP") (class "Default")
      (node (ref "TP8") (pin "TP") (pinfunction "TP_TP") (pintype "input"))
      (node (ref "U2") (pin "55") (pinfunction "(A10)PC2_55") (pintype "bidirectional"))
      (node (ref "U7") (pin "17") (pinfunction "STEP_17") (pintype "input"))
    )
    (net (code "130") (name "GND") (class "Default")
      (node (ref "C1") (pin "2") (pinfunction "2_2") (pintype "passive"))
      (node (ref "C17") (pin "2") (pinfunction "2_2") (pintype "passive"))
      (node (ref "C18") (pin "2") (pinfunction "2_2") (pintype "passive"))
      (node (ref "C23") (pin "2") (pinfunction "2_2") (pintype "passive"))
      (node (ref "C24") (pin "2") (pinfunction "2_2") (pintype "passive"))
      (node (ref "C25") (pin "2") (pinfunction "2_2") (pintype "passive"))
      (node (ref "C26") (pin "2") (pinfunction "2_2") (pintype "passive"))
      (node (ref "C29") (pin "2") (pinfunction "2_2") (pintype "passive"))
      (node (ref "C3") (pin "2") (pinfunction "2_2") (pintype "passive"))
      (node (ref "C30") (pin "2") (pinfunction "2_2") (pintype "passive"))
      (node (ref "C31") (pin "1") (pinfunction "1_1") (pintype "passive"))
      (node (ref "C34") (pin "2") (pinfunction "2_2") (pintype "passive"))
      (node (ref "C36") (pin "1") (pinfunction "1_1") (pintype "passive"))
      (node (ref "C39") (pin "2") (pinfunction "2_2") (pintype "passive"))
      (node (ref "C4") (pin "2") (pinfunction "2_2") (pintype "passive"))
      (node (ref "C40") (pin "2") (pinfunction "2_2") (pintype "passive"))
      (node (ref "C41") (pin "1") (pinfunction "1_1") (pintype "passive"))
      (node (ref "C44") (pin "2") (pinfunction "2_2") (pintype "passive"))
      (node (ref "C45") (pin "2") (pinfunction "2_2") (pintype "passive"))
      (node (ref "C46") (pin "1") (pinfunction "1_1") (pintype "passive"))
      (node (ref "C49") (pin "2") (pinfunction "2_2") (pintype "passive"))
      (node (ref "C51") (pin "1") (pinfunction "1_1") (pintype "passive"))
      (node (ref "C52") (pin "2") (pinfunction "2_2") (pintype "passive"))
      (node (ref "C53") (pin "2") (pinfunction "2_2") (pintype "passive"))
      (node (ref "C54") (pin "2") (pinfunction "2_2") (pintype "passive"))
      (node (ref "C55") (pin "2") (pinfunction "2_2") (pintype "passive"))
      (node (ref "C56") (pin "2") (pinfunction "2_2") (pintype "passive"))
      (node (ref "C57") (pin "2") (pinfunction "2_2") (pintype "passive"))
      (node (ref "C58") (pin "2") (pinfunction "2_2") (pintype "passive"))
      (node (ref "C59") (pin "2") (pinfunction "2_2") (pintype "passive"))
      (node (ref "C6") (pin "2") (pinfunction "2_2") (pintype "passive"))
      (node (ref "C60") (pin "2") (pinfunction "2_2") (pintype "passive"))
      (node (ref "C62") (pin "2") (pinfunction "2_2") (pintype "passive"))
      (node (ref "C64") (pin "2") (pinfunction "2_2") (pintype "passive"))
      (node (ref "C65") (pin "-") (pinfunction "-_-") (pintype "passive"))
      (node (ref "C66") (pin "-") (pinfunction "-_-") (pintype "passive"))
      (node (ref "C68") (pin "1") (pinfunction "1_1") (pintype "passive"))
      (node (ref "C69") (pin "2") (pinfunction "2_2") (pintype "passive"))
      (node (ref "C7") (pin "2") (pinfunction "2_2") (pintype "passive"))
      (node (ref "C71") (pin "2") (pinfunction "2_2") (pintype "passive"))
      (node (ref "C72") (pin "2") (pinfunction "2_2") (pintype "passive"))
      (node (ref "C73") (pin "2") (pinfunction "2_2") (pintype "passive"))
      (node (ref "C74") (pin "2") (pinfunction "2_2") (pintype "passive"))
      (node (ref "C75") (pin "2") (pinfunction "2_2") (pintype "passive"))
      (node (ref "C76") (pin "-") (pinfunction "-_-") (pintype "passive"))
      (node (ref "C8") (pin "2") (pinfunction "2_2") (pintype "passive"))
      (node (ref "C9") (pin "2") (pinfunction "2_2") (pintype "passive"))
      (node (ref "D12") (pin "A") (pinfunction "A_A") (pintype "passive"))
      (node (ref "D13") (pin "A") (pinfunction "A_A") (pintype "passive"))
      (node (ref "D15") (pin "A") (pinfunction "A_A") (pintype "passive"))
      (node (ref "D17") (pin "A") (pinfunction "A_A") (pintype "passive"))
      (node (ref "D19") (pin "A") (pinfunction "A_A") (pintype "passive"))
      (node (ref "D2") (pin "A") (pinfunction "A_A") (pintype "passive"))
      (node (ref "D20") (pin "A") (pinfunction "A_A") (pintype "passive"))
      (node (ref "D7") (pin "A") (pinfunction "A_A") (pintype "passive"))
      (node (ref "D8") (pin "A") (pinfunction "A_A") (pintype "passive"))
      (node (ref "H1") (pin "P$1") (pinfunction "P$1_P$1") (pintype "bidirectional"))
      (node (ref "H1") (pin "P$17") (pinfunction "P$1_P$17") (pintype "bidirectional"))
      (node (ref "H1") (pin "P$18") (pinfunction "P$1_P$18") (pintype "bidirectional"))
      (node (ref "H1") (pin "P$19") (pinfunction "P$1_P$19") (pintype "bidirectional"))
      (node (ref "H1") (pin "P$2") (pinfunction "P$1_P$2") (pintype "bidirectional"))
      (node (ref "H1") (pin "P$20") (pinfunction "P$1_P$20") (pintype "bidirectional"))
      (node (ref "H1") (pin "P$21") (pinfunction "P$1_P$21") (pintype "bidirectional"))
      (node (ref "H1") (pin "P$22") (pinfunction "P$1_P$22") (pintype "bidirectional"))
      (node (ref "H1") (pin "P$23") (pinfunction "P$1_P$23") (pintype "bidirectional"))
      (node (ref "H1") (pin "P$24") (pinfunction "P$1_P$24") (pintype "bidirectional"))
      (node (ref "H1") (pin "P$3") (pinfunction "P$1_P$3") (pintype "bidirectional"))
      (node (ref "H1") (pin "P$4") (pinfunction "P$1_P$4") (pintype "bidirectional"))
      (node (ref "H1") (pin "P$5") (pinfunction "P$1_P$5") (pintype "bidirectional"))
      (node (ref "H1") (pin "P$6") (pinfunction "P$1_P$6") (pintype "bidirectional"))
      (node (ref "H1") (pin "P$7") (pinfunction "P$1_P$7") (pintype "bidirectional"))
      (node (ref "H1") (pin "P$8") (pinfunction "P$1_P$8") (pintype "bidirectional"))
      (node (ref "H2") (pin "P$1") (pinfunction "P$1_P$1") (pintype "bidirectional"))
      (node (ref "H2") (pin "P$17") (pinfunction "P$1_P$17") (pintype "bidirectional"))
      (node (ref "H2") (pin "P$18") (pinfunction "P$1_P$18") (pintype "bidirectional"))
      (node (ref "H2") (pin "P$19") (pinfunction "P$1_P$19") (pintype "bidirectional"))
      (node (ref "H2") (pin "P$2") (pinfunction "P$1_P$2") (pintype "bidirectional"))
      (node (ref "H2") (pin "P$20") (pinfunction "P$1_P$20") (pintype "bidirectional"))
      (node (ref "H2") (pin "P$21") (pinfunction "P$1_P$21") (pintype "bidirectional"))
      (node (ref "H2") (pin "P$22") (pinfunction "P$1_P$22") (pintype "bidirectional"))
      (node (ref "H2") (pin "P$23") (pinfunction "P$1_P$23") (pintype "bidirectional"))
      (node (ref "H2") (pin "P$24") (pinfunction "P$1_P$24") (pintype "bidirectional"))
      (node (ref "H2") (pin "P$3") (pinfunction "P$1_P$3") (pintype "bidirectional"))
      (node (ref "H2") (pin "P$4") (pinfunction "P$1_P$4") (pintype "bidirectional"))
      (node (ref "H2") (pin "P$5") (pinfunction "P$1_P$5") (pintype "bidirectional"))
      (node (ref "H2") (pin "P$6") (pinfunction "P$1_P$6") (pintype "bidirectional"))
      (node (ref "H2") (pin "P$7") (pinfunction "P$1_P$7") (pintype "bidirectional"))
      (node (ref "H2") (pin "P$8") (pinfunction "P$1_P$8") (pintype "bidirectional"))
      (node (ref "H3") (pin "P$1") (pinfunction "P$1_P$1") (pintype "bidirectional"))
      (node (ref "H3") (pin "P$17") (pinfunction "P$1_P$17") (pintype "bidirectional"))
      (node (ref "H3") (pin "P$18") (pinfunction "P$1_P$18") (pintype "bidirectional"))
      (node (ref "H3") (pin "P$19") (pinfunction "P$1_P$19") (pintype "bidirectional"))
      (node (ref "H3") (pin "P$2") (pinfunction "P$1_P$2") (pintype "bidirectional"))
      (node (ref "H3") (pin "P$20") (pinfunction "P$1_P$20") (pintype "bidirectional"))
      (node (ref "H3") (pin "P$21") (pinfunction "P$1_P$21") (pintype "bidirectional"))
      (node (ref "H3") (pin "P$22") (pinfunction "P$1_P$22") (pintype "bidirectional"))
      (node (ref "H3") (pin "P$23") (pinfunction "P$1_P$23") (pintype "bidirectional"))
      (node (ref "H3") (pin "P$24") (pinfunction "P$1_P$24") (pintype "bidirectional"))
      (node (ref "H3") (pin "P$3") (pinfunction "P$1_P$3") (pintype "bidirectional"))
      (node (ref "H3") (pin "P$4") (pinfunction "P$1_P$4") (pintype "bidirectional"))
      (node (ref "H3") (pin "P$5") (pinfunction "P$1_P$5") (pintype "bidirectional"))
      (node (ref "H3") (pin "P$6") (pinfunction "P$1_P$6") (pintype "bidirectional"))
      (node (ref "H3") (pin "P$7") (pinfunction "P$1_P$7") (pintype "bidirectional"))
      (node (ref "H3") (pin "P$8") (pinfunction "P$1_P$8") (pintype "bidirectional"))
      (node (ref "H4") (pin "P$1") (pinfunction "P$1_P$1") (pintype "bidirectional"))
      (node (ref "H4") (pin "P$17") (pinfunction "P$1_P$17") (pintype "bidirectional"))
      (node (ref "H4") (pin "P$18") (pinfunction "P$1_P$18") (pintype "bidirectional"))
      (node (ref "H4") (pin "P$19") (pinfunction "P$1_P$19") (pintype "bidirectional"))
      (node (ref "H4") (pin "P$2") (pinfunction "P$1_P$2") (pintype "bidirectional"))
      (node (ref "H4") (pin "P$20") (pinfunction "P$1_P$20") (pintype "bidirectional"))
      (node (ref "H4") (pin "P$21") (pinfunction "P$1_P$21") (pintype "bidirectional"))
      (node (ref "H4") (pin "P$22") (pinfunction "P$1_P$22") (pintype "bidirectional"))
      (node (ref "H4") (pin "P$23") (pinfunction "P$1_P$23") (pintype "bidirectional"))
      (node (ref "H4") (pin "P$24") (pinfunction "P$1_P$24") (pintype "bidirectional"))
      (node (ref "H4") (pin "P$3") (pinfunction "P$1_P$3") (pintype "bidirectional"))
      (node (ref "H4") (pin "P$4") (pinfunction "P$1_P$4") (pintype "bidirectional"))
      (node (ref "H4") (pin "P$5") (pinfunction "P$1_P$5") (pintype "bidirectional"))
      (node (ref "H4") (pin "P$6") (pinfunction "P$1_P$6") (pintype "bidirectional"))
      (node (ref "H4") (pin "P$7") (pinfunction "P$1_P$7") (pintype "bidirectional"))
      (node (ref "H4") (pin "P$8") (pinfunction "P$1_P$8") (pintype "bidirectional"))
      (node (ref "JP3") (pin "1") (pinfunction "1_1") (pintype "passive"))
      (node (ref "LED1") (pin "C") (pinfunction "C_C") (pintype "passive"))
      (node (ref "LED7") (pin "C") (pinfunction "C_C") (pintype "passive"))
      (node (ref "Q1") (pin "1") (pinfunction "S_1") (pintype "passive"))
      (node (ref "Q1") (pin "2") (pinfunction "S_2") (pintype "passive"))
      (node (ref "Q1") (pin "3") (pinfunction "S_3") (pintype "passive"))
      (node (ref "Q2") (pin "1") (pinfunction "S_1") (pintype "passive"))
      (node (ref "Q2") (pin "2") (pinfunction "S_2") (pintype "passive"))
      (node (ref "Q2") (pin "3") (pinfunction "S_3") (pintype "passive"))
      (node (ref "Q3") (pin "1") (pinfunction "S_1") (pintype "passive"))
      (node (ref "Q3") (pin "2") (pinfunction "S_2") (pintype "passive"))
      (node (ref "Q3") (pin "3") (pinfunction "S_3") (pintype "passive"))
      (node (ref "Q4") (pin "2") (pinfunction "S_2") (pintype "passive"))
      (node (ref "Q5") (pin "1") (pinfunction "S_1") (pintype "passive"))
      (node (ref "Q5") (pin "2") (pinfunction "S_2") (pintype "passive"))
      (node (ref "Q5") (pin "3") (pinfunction "S_3") (pintype "passive"))
      (node (ref "Q8") (pin "2") (pinfunction "S_2") (pintype "passive"))
      (node (ref "R10") (pin "2") (pinfunction "2_2") (pintype "passive"))
      (node (ref "R11") (pin "2") (pinfunction "2_2") (pintype "passive"))
      (node (ref "R12") (pin "1") (pinfunction "1_1") (pintype "passive"))
      (node (ref "R14") (pin "2") (pinfunction "2_2") (pintype "passive"))
      (node (ref "R15") (pin "2") (pinfunction "2_2") (pintype "passive"))
      (node (ref "R17") (pin "1") (pinfunction "1_1") (pintype "passive"))
      (node (ref "R18") (pin "1") (pinfunction "1_1") (pintype "passive"))
      (node (ref "R19") (pin "2") (pinfunction "2_2") (pintype "passive"))
      (node (ref "R20") (pin "2") (pinfunction "2_2") (pintype "passive"))
      (node (ref "R22") (pin "1") (pinfunction "1_1") (pintype "passive"))
      (node (ref "R23") (pin "2") (pinfunction "2_2") (pintype "passive"))
      (node (ref "R24") (pin "2") (pinfunction "2_2") (pintype "passive"))
      (node (ref "R26") (pin "1") (pinfunction "1_1") (pintype "passive"))
      (node (ref "R4") (pin "2") (pinfunction "2_2") (pintype "passive"))
      (node (ref "R43") (pin "2") (pinfunction "2_2") (pintype "passive"))
      (node (ref "R49") (pin "2") (pinfunction "2_2") (pintype "passive"))
      (node (ref "R52") (pin "2") (pinfunction "2_2") (pintype "passive"))
      (node (ref "R54") (pin "2") (pinfunction "2_2") (pintype "passive"))
      (node (ref "R57") (pin "2") (pinfunction "2_2") (pintype "passive"))
      (node (ref "R7") (pin "2") (pinfunction "2_2") (pintype "passive"))
      (node (ref "R71") (pin "2") (pinfunction "2_2") (pintype "passive"))
      (node (ref "R8") (pin "2") (pinfunction "2_2") (pintype "passive"))
      (node (ref "S1") (pin "2") (pinfunction "S_2") (pintype "passive"))
      (node (ref "TP24") (pin "1") (pinfunction "1_1") (pintype "passive"))
      (node (ref "U10") (pin "15") (pinfunction "GND2A_15") (pintype "bidirectional"))
      (node (ref "U10") (pin "9") (pinfunction "GND2B_9") (pintype "bidirectional"))
      (node (ref "U2") (pin "11") (pinfunction "GND_11") (pintype "power_in"))
      (node (ref "U2") (pin "32") (pinfunction "GND1_32") (pintype "power_in"))
      (node (ref "U2") (pin "62") (pinfunction "GND2_62") (pintype "power_in"))
      (node (ref "U2") (pin "81") (pinfunction "GND3_81") (pintype "power_in"))
      (node (ref "U2") (pin "99") (pinfunction "AGND_99") (pintype "power_in"))
      (node (ref "U3") (pin "6") (pinfunction "GND_6") (pintype "bidirectional"))
      (node (ref "U3") (pin "9") (pinfunction "PAD_9") (pintype "bidirectional"))
      (node (ref "U4") (pin "P03") (pinfunction "B6_P03") (pintype "bidirectional"))
      (node (ref "U4") (pin "P04") (pinfunction "GND_P04") (pintype "bidirectional"))
      (node (ref "U4") (pin "P09") (pinfunction "VSS_P09") (pintype "bidirectional"))
      (node (ref "U4") (pin "P10") (pinfunction "B5_P10") (pintype "bidirectional"))
      (node (ref "U4") (pin "P13") (pinfunction "B3_P13") (pintype "bidirectional"))
      (node (ref "U4") (pin "P16") (pinfunction "B1_P16") (pintype "bidirectional"))
      (node (ref "U4") (pin "P21") (pinfunction "B2_P21") (pintype "bidirectional"))
      (node (ref "U4") (pin "P24") (pinfunction "B4_P24") (pintype "bidirectional"))
      (node (ref "U5") (pin "19") (pinfunction "GND2_19") (pintype "power_in"))
      (node (ref "U5") (pin "33") (pinfunction "TH-PAD_33") (pintype "power_in"))
      (node (ref "U5") (pin "6") (pinfunction "GND1_6") (pintype "power_in"))
      (node (ref "U6") (pin "19") (pinfunction "GND2_19") (pintype "power_in"))
      (node (ref "U6") (pin "33") (pinfunction "TH-PAD_33") (pintype "power_in"))
      (node (ref "U6") (pin "6") (pinfunction "GND1_6") (pintype "power_in"))
      (node (ref "U7") (pin "19") (pinfunction "GND2_19") (pintype "power_in"))
      (node (ref "U7") (pin "33") (pinfunction "TH-PAD_33") (pintype "power_in"))
      (node (ref "U7") (pin "6") (pinfunction "GND1_6") (pintype "power_in"))
      (node (ref "U8") (pin "19") (pinfunction "GND2_19") (pintype "power_in"))
      (node (ref "U8") (pin "33") (pinfunction "TH-PAD_33") (pintype "power_in"))
      (node (ref "U8") (pin "6") (pinfunction "GND1_6") (pintype "power_in"))
      (node (ref "U9") (pin "19") (pinfunction "GND2_19") (pintype "power_in"))
      (node (ref "U9") (pin "33") (pinfunction "TH-PAD_33") (pintype "power_in"))
      (node (ref "U9") (pin "6") (pinfunction "GND1_6") (pintype "power_in"))
      (node (ref "X1") (pin "1") (pinfunction "S_1") (pintype "passive"))
      (node (ref "X10") (pin "2") (pinfunction "S_2") (pintype "passive"))
      (node (ref "X12") (pin "7") (pinfunction "7_7") (pintype "passive"))
      (node (ref "X13") (pin "3") (pinfunction "3_3") (pintype "passive"))
      (node (ref "X13") (pin "4") (pinfunction "4_4") (pintype "passive"))
      (node (ref "X18") (pin "6") (pinfunction "6_6") (pintype "passive"))
      (node (ref "X20") (pin "2") (pinfunction "2_2") (pintype "passive"))
      (node (ref "X21") (pin "2") (pinfunction "S_2") (pintype "passive"))
      (node (ref "X22") (pin "2") (pinfunction "S_2") (pintype "passive"))
      (node (ref "X23") (pin "2") (pinfunction "S_2") (pintype "passive"))
      (node (ref "X24") (pin "2") (pinfunction "S_2") (pintype "passive"))
      (node (ref "X25") (pin "2") (pinfunction "S_2") (pintype "passive"))
      (node (ref "X26") (pin "2") (pinfunction "S_2") (pintype "passive"))
      (node (ref "X27") (pin "1") (pinfunction "S_1") (pintype "passive"))
      (node (ref "X28") (pin "1") (pinfunction "S_1") (pintype "passive"))
      (node (ref "X29") (pin "1") (pinfunction "S_1") (pintype "passive"))
      (node (ref "X3") (pin "1") (pinfunction "S_1") (pintype "passive"))
      (node (ref "X30") (pin "1") (pinfunction "S_1") (pintype "passive"))
      (node (ref "X31") (pin "2") (pinfunction "2_2") (pintype "passive"))
      (node (ref "X32") (pin "2") (pinfunction "2_2") (pintype "passive"))
      (node (ref "X33") (pin "2") (pinfunction "1_2") (pintype "passive"))
      (node (ref "X33") (pin "4") (pinfunction "1_4") (pintype "passive"))
      (node (ref "X33") (pin "6") (pinfunction "1_6") (pintype "passive"))
      (node (ref "X34") (pin "2") (pinfunction "2_2") (pintype "passive"))
      (node (ref "X39") (pin "2") (pinfunction "2_2") (pintype "passive"))
      (node (ref "X40") (pin "2") (pinfunction "2_2") (pintype "passive"))
      (node (ref "Y1") (pin "2") (pinfunction "GND_2") (pintype "passive"))
      (node (ref "Y1") (pin "4") (pinfunction "GND_4") (pintype "passive"))
    )
    (net (code "131") (name "GND1") (class "Default")
      (node (ref "C11") (pin "2") (pinfunction "2_2") (pintype "passive"))
      (node (ref "C12") (pin "2") (pinfunction "2_2") (pintype "passive"))
      (node (ref "C13") (pin "2") (pinfunction "2_2") (pintype "passive"))
      (node (ref "C14") (pin "2") (pinfunction "2_2") (pintype "passive"))
      (node (ref "C15") (pin "2") (pinfunction "2_2") (pintype "passive"))
      (node (ref "C16") (pin "2") (pinfunction "2_2") (pintype "passive"))
      (node (ref "C2") (pin "1") (pinfunction "1_1") (pintype "passive"))
      (node (ref "C63") (pin "2") (pinfunction "2_2") (pintype "passive"))
      (node (ref "C67") (pin "1") (pinfunction "1_1") (pintype "passive"))
      (node (ref "C70") (pin "2") (pinfunction "2_2") (pintype "passive"))
      (node (ref "R72") (pin "1") (pinfunction "1_1") (pintype "passive"))
      (node (ref "U1") (pin "28") (pinfunction "UGND_28") (pintype "power_in"))
      (node (ref "U1") (pin "3") (pinfunction "GND_3") (pintype "power_in"))
      (node (ref "U1") (pin "33") (pinfunction "PAD_33") (pintype "power_in"))
      (node (ref "U10") (pin "2") (pinfunction "GND1A_2") (pintype "bidirectional"))
      (node (ref "U10") (pin "4") (pinfunction "VIB_4") (pintype "bidirectional"))
      (node (ref "U10") (pin "8") (pinfunction "GND1B_8") (pintype "bidirectional"))
      (node (ref "X16") (pin "3") (pinfunction "3_3") (pintype "passive"))
      (node (ref "X16") (pin "4") (pinfunction "4_4") (pintype "passive"))
      (node (ref "X17") (pin "6") (pinfunction "6_6") (pintype "passive"))
      (node (ref "X2") (pin "4") (pinfunction "4_4") (pintype "bidirectional"))
      (node (ref "Y2") (pin "2") (pinfunction "GND_2") (pintype "passive"))
      (node (ref "Y2") (pin "4") (pinfunction "GND_4") (pintype "passive"))
    )
    (net (code "132") (name "Net-(F2-PadP$1)") (class "Default")
      (node (ref "F2") (pin "P$1") (pinfunction "P$1_P$1") (pintype "bidirectional"))
      (node (ref "X33") (pin "1") (pinfunction "1_1") (pintype "passive"))
    )
    (net (code "133") (name "Net-(F4-1)") (class "Default")
      (node (ref "F4") (pin "P$1") (pinfunction "1_P$1") (pintype "passive"))
      (node (ref "X33") (pin "5") (pinfunction "1_5") (pintype "passive"))
    )
    (net (code "134") (name "Net-(L3-1)") (class "Default")
      (node (ref "C35") (pin "2") (pinfunction "2_2") (pintype "passive"))
      (node (ref "D20") (pin "C") (pinfunction "C_C") (pintype "passive"))
      (node (ref "L3") (pin "P$1") (pinfunction "1_P$1") (pintype "passive"))
      (node (ref "U3") (pin "8") (pinfunction "SWITCH_8") (pintype "bidirectional"))
    )
    (net (code "135") (name "Net-(LED1-PadA)") (class "Default")
      (node (ref "LED1") (pin "A") (pinfunction "A_A") (pintype "passive"))
      (node (ref "R33") (pin "2") (pinfunction "2_2") (pintype "passive"))
    )
    (net (code "136") (name "Net-(LED2-PadA)") (class "Default")
      (node (ref "LED2") (pin "A") (pinfunction "A_A") (pintype "passive"))
      (node (ref "R40") (pin "1") (pinfunction "1_1") (pintype "passive"))
    )
    (net (code "137") (name "Net-(LED3-PadA)") (class "Default")
      (node (ref "LED3") (pin "A") (pinfunction "A_A") (pintype "passive"))
      (node (ref "R50") (pin "1") (pinfunction "1_1") (pintype "passive"))
    )
    (net (code "138") (name "Net-(LED4-PadA)") (class "Default")
      (node (ref "LED4") (pin "A") (pinfunction "A_A") (pintype "passive"))
      (node (ref "R41") (pin "1") (pinfunction "1_1") (pintype "passive"))
    )
    (net (code "139") (name "Net-(LED5-PadA)") (class "Default")
      (node (ref "LED5") (pin "A") (pinfunction "A_A") (pintype "passive"))
      (node (ref "R55") (pin "1") (pinfunction "1_1") (pintype "passive"))
    )
    (net (code "140") (name "Net-(LED6-PadA)") (class "Default")
      (node (ref "LED6") (pin "A") (pinfunction "A_A") (pintype "passive"))
      (node (ref "R58") (pin "1") (pinfunction "1_1") (pintype "passive"))
    )
    (net (code "141") (name "Net-(LED7-PadA)") (class "Default")
      (node (ref "LED7") (pin "A") (pinfunction "A_A") (pintype "passive"))
      (node (ref "R35") (pin "2") (pinfunction "2_2") (pintype "passive"))
    )
    (net (code "142") (name "Net-(LED8-PadA)") (class "Default")
      (node (ref "LED8") (pin "A") (pinfunction "A_A") (pintype "passive"))
      (node (ref "R69") (pin "1") (pinfunction "1_1") (pintype "passive"))
    )
    (net (code "143") (name "Net-(Q1-D)") (class "Default")
      (node (ref "D6") (pin "A") (pinfunction "A_A") (pintype "passive"))
      (node (ref "LED2") (pin "C") (pinfunction "C_C") (pintype "passive"))
      (node (ref "Q1") (pin "MB") (pinfunction "D_MB") (pintype "passive"))
      (node (ref "X11") (pin "1") (pinfunction "1_1") (pintype "passive"))
      (node (ref "X35") (pin "1") (pinfunction "1_1") (pintype "passive"))
    )
    (net (code "144") (name "Net-(Q1-G)") (class "Default")
      (node (ref "Q1") (pin "4") (pinfunction "G_4") (pintype "passive"))
      (node (ref "R42") (pin "2") (pinfunction "2_2") (pintype "passive"))
    )
    (net (code "145") (name "Net-(Q2-D)") (class "Default")
      (node (ref "D3") (pin "A") (pinfunction "A_A") (pintype "passive"))
      (node (ref "LED3") (pin "C") (pinfunction "C_C") (pintype "passive"))
      (node (ref "Q2") (pin "MB") (pinfunction "D_MB") (pintype "passive"))
      (node (ref "X11") (pin "3") (pinfunction "1_3") (pintype "passive"))
      (node (ref "X36") (pin "1") (pinfunction "1_1") (pintype "passive"))
    )
    (net (code "146") (name "Net-(Q2-G)") (class "Default")
      (node (ref "Q2") (pin "4") (pinfunction "G_4") (pintype "passive"))
      (node (ref "R48") (pin "2") (pinfunction "2_2") (pintype "passive"))
    )
    (net (code "147") (name "Net-(Q3-D)") (class "Default")
      (node (ref "D1") (pin "A") (pinfunction "A_A") (pintype "passive"))
      (node (ref "LED4") (pin "C") (pinfunction "C_C") (pintype "passive"))
      (node (ref "Q3") (pin "MB") (pinfunction "D_MB") (pintype "passive"))
      (node (ref "X11") (pin "5") (pinfunction "1_5") (pintype "passive"))
      (node (ref "X37") (pin "1") (pinfunction "1_1") (pintype "passive"))
    )
    (net (code "148") (name "Net-(Q3-G)") (class "Default")
      (node (ref "Q3") (pin "4") (pinfunction "G_4") (pintype "passive"))
      (node (ref "R51") (pin "2") (pinfunction "2_2") (pintype "passive"))
    )
    (net (code "149") (name "Net-(Q4-D)") (class "Default")
      (node (ref "LED5") (pin "C") (pinfunction "C_C") (pintype "passive"))
      (node (ref "Q4") (pin "3") (pinfunction "D_3") (pintype "passive"))
      (node (ref "X11") (pin "7") (pinfunction "1_7") (pintype "passive"))
    )
    (net (code "150") (name "Net-(Q4-G)") (class "Default")
      (node (ref "Q4") (pin "1") (pinfunction "G_1") (pintype "passive"))
      (node (ref "R53") (pin "2") (pinfunction "2_2") (pintype "passive"))
    )
    (net (code "151") (name "Net-(Q5-D)") (class "Default")
      (node (ref "D10") (pin "A") (pinfunction "A_A") (pintype "passive"))
      (node (ref "LED6") (pin "C") (pinfunction "C_C") (pintype "passive"))
      (node (ref "Q5") (pin "MB") (pinfunction "D_MB") (pintype "passive"))
      (node (ref "X11") (pin "9") (pinfunction "1_9") (pintype "passive"))
      (node (ref "X38") (pin "1") (pinfunction "1_1") (pintype "passive"))
    )
    (net (code "152") (name "Net-(Q5-G)") (class "Default")
      (node (ref "Q5") (pin "4") (pinfunction "G_4") (pintype "passive"))
      (node (ref "R56") (pin "2") (pinfunction "2_2") (pintype "passive"))
    )
    (net (code "153") (name "Net-(Q8-D)") (class "Default")
      (node (ref "LED8") (pin "C") (pinfunction "C_C") (pintype "passive"))
      (node (ref "Q8") (pin "3") (pinfunction "D_3") (pintype "passive"))
      (node (ref "X9") (pin "1") (pinfunction "S_1") (pintype "passive"))
    )
    (net (code "154") (name "Net-(Q8-G)") (class "Default")
      (node (ref "Q8") (pin "1") (pinfunction "G_1") (pintype "passive"))
      (node (ref "R70") (pin "2") (pinfunction "2_2") (pintype "passive"))
    )
    (net (code "155") (name "Net-(RN5B-2)") (class "Default")
      (node (ref "LED10") (pin "A") (pinfunction "A_A") (pintype "passive"))
      (node (ref "RN5") (pin "7") (pinfunction "2_7") (pintype "passive"))
    )
    (net (code "156") (name "Net-(RN5C-2)") (class "Default")
      (node (ref "LED9") (pin "A") (pinfunction "A_A") (pintype "passive"))
      (node (ref "RN5") (pin "6") (pinfunction "2_6") (pintype "passive"))
    )
    (net (code "157") (name "Net-(U1-XTAL1)") (class "Default")
      (node (ref "C13") (pin "1") (pinfunction "1_1") (pintype "passive"))
      (node (ref "U1") (pin "1") (pinfunction "XTAL1_1") (pintype "bidirectional"))
      (node (ref "Y2") (pin "1") (pinfunction "C1_1") (pintype "passive"))
    )
    (net (code "158") (name "Net-(U1-XTAL2(PC0))") (class "Default")
      (node (ref "C12") (pin "1") (pinfunction "1_1") (pintype "passive"))
      (node (ref "U1") (pin "2") (pinfunction "XTAL2(PC0)_2") (pintype "bidirectional"))
      (node (ref "Y2") (pin "3") (pinfunction "C2_3") (pintype "passive"))
    )
    (net (code "159") (name "Net-(U2-AVCC)") (class "Default")
      (node (ref "C26") (pin "1") (pinfunction "1_1") (pintype "passive"))
      (node (ref "L2") (pin "2") (pinfunction "2_2") (pintype "passive"))
      (node (ref "U2") (pin "100") (pinfunction "AVCC_100") (pintype "power_in"))
    )
    (net (code "160") (name "Net-(U2-XTAL1)") (class "Default")
      (node (ref "C57") (pin "1") (pinfunction "1_1") (pintype "passive"))
      (node (ref "U2") (pin "34") (pinfunction "XTAL1_34") (pintype "input"))
      (node (ref "Y1") (pin "1") (pinfunction "C1_1") (pintype "passive"))
    )
    (net (code "161") (name "Net-(U2-XTAL2)") (class "Default")
      (node (ref "C58") (pin "1") (pinfunction "1_1") (pintype "passive"))
      (node (ref "U2") (pin "33") (pinfunction "XTAL2_33") (pintype "output"))
      (node (ref "Y1") (pin "3") (pinfunction "C2_3") (pintype "passive"))
    )
    (net (code "162") (name "Net-(U3-BOOT)") (class "Default")
      (node (ref "C35") (pin "1") (pinfunction "1_1") (pintype "passive"))
      (node (ref "U3") (pin "1") (pinfunction "BOOT_1") (pintype "bidirectional"))
    )
    (net (code "163") (name "Net-(U3-ENABLE)") (class "Default")
      (node (ref "JP3") (pin "2") (pinfunction "2_2") (pintype "passive"))
      (node (ref "R3") (pin "1") (pinfunction "1_1") (pintype "passive"))
      (node (ref "U3") (pin "5") (pinfunction "ENABLE_5") (pintype "bidirectional"))
    )
    (net (code "164") (name "Net-(U3-FEEDBACK)") (class "Default")
      (node (ref "R11") (pin "1") (pinfunction "1_1") (pintype "passive"))
      (node (ref "R13") (pin "1") (pinfunction "1_1") (pintype "passive"))
      (node (ref "U3") (pin "4") (pinfunction "FEEDBACK_4") (pintype "bidirectional"))
    )
    (net (code "165") (name "Net-(U4-A1)") (class "Default")
      (node (ref "R30") (pin "2") (pinfunction "2_2") (pintype "passive"))
      (node (ref "U4") (pin "P01") (pinfunction "A6_P01") (pintype "bidirectional"))
      (node (ref "U4") (pin "P12") (pinfunction "A5_P12") (pintype "bidirectional"))
      (node (ref "U4") (pin "P15") (pinfunction "A3_P15") (pintype "bidirectional"))
      (node (ref "U4") (pin "P18") (pinfunction "A1_P18") (pintype "bidirectional"))
      (node (ref "U4") (pin "P19") (pinfunction "A2_P19") (pintype "bidirectional"))
      (node (ref "U4") (pin "P22") (pinfunction "A4_P22") (pintype "bidirectional"))
    )
    (net (code "166") (name "Net-(U5-CP1)") (class "Default")
      (node (ref "C28") (pin "1") (pinfunction "1_1") (pintype "passive"))
      (node (ref "U5") (pin "7") (pinfunction "CP1_7") (pintype "bidirectional"))
    )
    (net (code "167") (name "Net-(U5-CP2)") (class "Default")
      (node (ref "C28") (pin "2") (pinfunction "2_2") (pintype "passive"))
      (node (ref "U5") (pin "8") (pinfunction "CP2_8") (pintype "bidirectional"))
    )
    (net (code "168") (name "Net-(U5-OUT1A)") (class "Default")
      (node (ref "U5") (pin "27") (pinfunction "OUT1A_27") (pintype "output"))
      (node (ref "X8") (pin "3") (pinfunction "1_3") (pintype "passive"))
    )
    (net (code "169") (name "Net-(U5-OUT1B)") (class "Default")
      (node (ref "U5") (pin "24") (pinfunction "OUT1B_24") (pintype "output"))
      (node (ref "X8") (pin "4") (pinfunction "1_4") (pintype "passive"))
    )
    (net (code "170") (name "Net-(U5-OUT2A)") (class "Default")
      (node (ref "U5") (pin "30") (pinfunction "OUT2A_30") (pintype "output"))
      (node (ref "X8") (pin "2") (pinfunction "1_2") (pintype "passive"))
    )
    (net (code "171") (name "Net-(U5-OUT2B)") (class "Default")
      (node (ref "U5") (pin "1") (pinfunction "OUT2B_1") (pintype "output"))
      (node (ref "X8") (pin "1") (pinfunction "1_1") (pintype "passive"))
    )
    (net (code "172") (name "Net-(U5-RESET)") (class "Default")
      (node (ref "C24") (pin "1") (pinfunction "1_1") (pintype "passive"))
      (node (ref "R29") (pin "1") (pinfunction "1_1") (pintype "passive"))
      (node (ref "U5") (pin "13") (pinfunction "RESET_13") (pintype "input"))
      (node (ref "U5") (pin "15") (pinfunction "SLEEP_15") (pintype "input"))
      (node (ref "U5") (pin "16") (pinfunction "VDD_16") (pintype "power_in"))
    )
    (net (code "173") (name "Net-(U5-ROSC)") (class "Default")
      (node (ref "R18") (pin "2") (pinfunction "2_2") (pintype "passive"))
      (node (ref "U5") (pin "14") (pinfunction "ROSC_14") (pintype "input"))
    )
    (net (code "174") (name "Net-(U5-SENSE1)") (class "Default")
      (node (ref "R7") (pin "1") (pinfunction "1_1") (pintype "passive"))
      (node (ref "U5") (pin "25") (pinfunction "SENSE1_25") (pintype "input"))
    )
    (net (code "175") (name "Net-(U5-SENSE2)") (class "Default")
      (node (ref "R4") (pin "1") (pinfunction "1_1") (pintype "passive"))
      (node (ref "U5") (pin "32") (pinfunction "SENSE2_32") (pintype "input"))
    )
    (net (code "176") (name "Net-(U5-VCP)") (class "Default")
      (node (ref "C27") (pin "2") (pinfunction "2_2") (pintype "passive"))
      (node (ref "U5") (pin "9") (pinfunction "VCP_9") (pintype "bidirectional"))
    )
    (net (code "177") (name "Net-(U5-VREG)") (class "Default")
      (node (ref "C31") (pin "2") (pinfunction "2_2") (pintype "passive"))
      (node (ref "U5") (pin "10") (pinfunction "VREG_10") (pintype "input"))
    )
    (net (code "178") (name "Net-(U6-CP1)") (class "Default")
      (node (ref "C33") (pin "1") (pinfunction "1_1") (pintype "passive"))
      (node (ref "U6") (pin "7") (pinfunction "CP1_7") (pintype "bidirectional"))
    )
    (net (code "179") (name "Net-(U6-CP2)") (class "Default")
      (node (ref "C33") (pin "2") (pinfunction "2_2") (pintype "passive"))
      (node (ref "U6") (pin "8") (pinfunction "CP2_8") (pintype "bidirectional"))
    )
    (net (code "180") (name "Net-(U6-OUT1A)") (class "Default")
      (node (ref "U6") (pin "27") (pinfunction "OUT1A_27") (pintype "output"))
      (node (ref "X4") (pin "3") (pinfunction "1_3") (pintype "passive"))
    )
    (net (code "181") (name "Net-(U6-OUT1B)") (class "Default")
      (node (ref "U6") (pin "24") (pinfunction "OUT1B_24") (pintype "output"))
      (node (ref "X4") (pin "4") (pinfunction "1_4") (pintype "passive"))
    )
    (net (code "182") (name "Net-(U6-OUT2A)") (class "Default")
      (node (ref "U6") (pin "30") (pinfunction "OUT2A_30") (pintype "output"))
      (node (ref "X4") (pin "2") (pinfunction "1_2") (pintype "passive"))
    )
    (net (code "183") (name "Net-(U6-OUT2B)") (class "Default")
      (node (ref "U6") (pin "1") (pinfunction "OUT2B_1") (pintype "output"))
      (node (ref "X4") (pin "1") (pinfunction "1_1") (pintype "passive"))
    )
    (net (code "184") (name "Net-(U6-RESET)") (class "Default")
      (node (ref "C23") (pin "1") (pinfunction "1_1") (pintype "passive"))
      (node (ref "R65") (pin "1") (pinfunction "1_1") (pintype "passive"))
      (node (ref "U6") (pin "13") (pinfunction "RESET_13") (pintype "input"))
      (node (ref "U6") (pin "15") (pinfunction "SLEEP_15") (pintype "input"))
      (node (ref "U6") (pin "16") (pinfunction "VDD_16") (pintype "power_in"))
    )
    (net (code "185") (name "Net-(U6-ROSC)") (class "Default")
      (node (ref "R12") (pin "2") (pinfunction "2_2") (pintype "passive"))
      (node (ref "U6") (pin "14") (pinfunction "ROSC_14") (pintype "input"))
    )
    (net (code "186") (name "Net-(U6-SENSE1)") (class "Default")
      (node (ref "R10") (pin "1") (pinfunction "1_1") (pintype "passive"))
      (node (ref "U6") (pin "25") (pinfunction "SENSE1_25") (pintype "input"))
    )
    (net (code "187") (name "Net-(U6-SENSE2)") (class "Default")
      (node (ref "R8") (pin "1") (pinfunction "1_1") (pintype "passive"))
      (node (ref "U6") (pin "32") (pinfunction "SENSE2_32") (pintype "input"))
    )
    (net (code "188") (name "Net-(U6-VCP)") (class "Default")
      (node (ref "C32") (pin "2") (pinfunction "2_2") (pintype "passive"))
      (node (ref "U6") (pin "9") (pinfunction "VCP_9") (pintype "bidirectional"))
    )
    (net (code "189") (name "Net-(U6-VREG)") (class "Default")
      (node (ref "C36") (pin "2") (pinfunction "2_2") (pintype "passive"))
      (node (ref "U6") (pin "10") (pinfunction "VREG_10") (pintype "input"))
    )
    (net (code "190") (name "Net-(U7-CP1)") (class "Default")
      (node (ref "C38") (pin "1") (pinfunction "1_1") (pintype "passive"))
      (node (ref "U7") (pin "7") (pinfunction "CP1_7") (pintype "bidirectional"))
    )
    (net (code "191") (name "Net-(U7-CP2)") (class "Default")
      (node (ref "C38") (pin "2") (pinfunction "2_2") (pintype "passive"))
      (node (ref "U7") (pin "8") (pinfunction "CP2_8") (pintype "bidirectional"))
    )
    (net (code "192") (name "Net-(U7-OUT1A)") (class "Default")
      (node (ref "U7") (pin "27") (pinfunction "OUT1A_27") (pintype "output"))
      (node (ref "X14") (pin "3") (pinfunction "1_3") (pintype "passive"))
      (node (ref "X15") (pin "3") (pinfunction "1_3") (pintype "passive"))
    )
    (net (code "193") (name "Net-(U7-OUT1B)") (class "Default")
      (node (ref "U7") (pin "24") (pinfunction "OUT1B_24") (pintype "output"))
      (node (ref "X14") (pin "4") (pinfunction "1_4") (pintype "passive"))
      (node (ref "X15") (pin "4") (pinfunction "1_4") (pintype "passive"))
    )
    (net (code "194") (name "Net-(U7-OUT2A)") (class "Default")
      (node (ref "U7") (pin "30") (pinfunction "OUT2A_30") (pintype "output"))
      (node (ref "X14") (pin "2") (pinfunction "1_2") (pintype "passive"))
      (node (ref "X15") (pin "2") (pinfunction "1_2") (pintype "passive"))
    )
    (net (code "195") (name "Net-(U7-OUT2B)") (class "Default")
      (node (ref "U7") (pin "1") (pinfunction "OUT2B_1") (pintype "output"))
      (node (ref "X14") (pin "1") (pinfunction "1_1") (pintype "passive"))
      (node (ref "X15") (pin "1") (pinfunction "1_1") (pintype "passive"))
    )
    (net (code "196") (name "Net-(U7-RESET)") (class "Default")
      (node (ref "C18") (pin "1") (pinfunction "1_1") (pintype "passive"))
      (node (ref "R66") (pin "1") (pinfunction "1_1") (pintype "passive"))
      (node (ref "U7") (pin "13") (pinfunction "RESET_13") (pintype "input"))
      (node (ref "U7") (pin "15") (pinfunction "SLEEP_15") (pintype "input"))
      (node (ref "U7") (pin "16") (pinfunction "VDD_16") (pintype "power_in"))
    )
    (net (code "197") (name "Net-(U7-ROSC)") (class "Default")
      (node (ref "R17") (pin "2") (pinfunction "2_2") (pintype "passive"))
      (node (ref "U7") (pin "14") (pinfunction "ROSC_14") (pintype "input"))
    )
    (net (code "198") (name "Net-(U7-SENSE1)") (class "Default")
      (node (ref "R15") (pin "1") (pinfunction "1_1") (pintype "passive"))
      (node (ref "U7") (pin "25") (pinfunction "SENSE1_25") (pintype "input"))
    )
    (net (code "199") (name "Net-(U7-SENSE2)") (class "Default")
      (node (ref "R14") (pin "1") (pinfunction "1_1") (pintype "passive"))
      (node (ref "U7") (pin "32") (pinfunction "SENSE2_32") (pintype "input"))
    )
    (net (code "200") (name "Net-(U7-VCP)") (class "Default")
      (node (ref "C37") (pin "2") (pinfunction "2_2") (pintype "passive"))
      (node (ref "U7") (pin "9") (pinfunction "VCP_9") (pintype "bidirectional"))
    )
    (net (code "201") (name "Net-(U7-VREG)") (class "Default")
      (node (ref "C41") (pin "2") (pinfunction "2_2") (pintype "passive"))
      (node (ref "U7") (pin "10") (pinfunction "VREG_10") (pintype "input"))
    )
    (net (code "202") (name "Net-(U8-CP1)") (class "Default")
      (node (ref "C43") (pin "1") (pinfunction "1_1") (pintype "passive"))
      (node (ref "U8") (pin "7") (pinfunction "CP1_7") (pintype "bidirectional"))
    )
    (net (code "203") (name "Net-(U8-CP2)") (class "Default")
      (node (ref "C43") (pin "2") (pinfunction "2_2") (pintype "passive"))
      (node (ref "U8") (pin "8") (pinfunction "CP2_8") (pintype "bidirectional"))
    )
    (net (code "204") (name "Net-(U8-OUT1A)") (class "Default")
      (node (ref "U8") (pin "27") (pinfunction "OUT1A_27") (pintype "output"))
      (node (ref "X6") (pin "3") (pinfunction "1_3") (pintype "passive"))
    )
    (net (code "205") (name "Net-(U8-OUT1B)") (class "Default")
      (node (ref "U8") (pin "24") (pinfunction "OUT1B_24") (pintype "output"))
      (node (ref "X6") (pin "4") (pinfunction "1_4") (pintype "passive"))
    )
    (net (code "206") (name "Net-(U8-OUT2A)") (class "Default")
      (node (ref "U8") (pin "30") (pinfunction "OUT2A_30") (pintype "output"))
      (node (ref "X6") (pin "2") (pinfunction "1_2") (pintype "passive"))
    )
    (net (code "207") (name "Net-(U8-OUT2B)") (class "Default")
      (node (ref "U8") (pin "1") (pinfunction "OUT2B_1") (pintype "output"))
      (node (ref "X6") (pin "1") (pinfunction "1_1") (pintype "passive"))
    )
    (net (code "208") (name "Net-(U8-RESET)") (class "Default")
      (node (ref "C17") (pin "1") (pinfunction "1_1") (pintype "passive"))
      (node (ref "R67") (pin "1") (pinfunction "1_1") (pintype "passive"))
      (node (ref "U8") (pin "13") (pinfunction "RESET_13") (pintype "input"))
      (node (ref "U8") (pin "15") (pinfunction "SLEEP_15") (pintype "input"))
      (node (ref "U8") (pin "16") (pinfunction "VDD_16") (pintype "power_in"))
    )
    (net (code "209") (name "Net-(U8-ROSC)") (class "Default")
      (node (ref "R22") (pin "2") (pinfunction "2_2") (pintype "passive"))
      (node (ref "U8") (pin "14") (pinfunction "ROSC_14") (pintype "input"))
    )
    (net (code "210") (name "Net-(U8-SENSE1)") (class "Default")
      (node (ref "R20") (pin "1") (pinfunction "1_1") (pintype "passive"))
      (node (ref "U8") (pin "25") (pinfunction "SENSE1_25") (pintype "input"))
    )
    (net (code "211") (name "Net-(U8-SENSE2)") (class "Default")
      (node (ref "R19") (pin "1") (pinfunction "1_1") (pintype "passive"))
      (node (ref "U8") (pin "32") (pinfunction "SENSE2_32") (pintype "input"))
    )
    (net (code "212") (name "Net-(U8-VCP)") (class "Default")
      (node (ref "C42") (pin "2") (pinfunction "2_2") (pintype "passive"))
      (node (ref "U8") (pin "9") (pinfunction "VCP_9") (pintype "bidirectional"))
    )
    (net (code "213") (name "Net-(U8-VREG)") (class "Default")
      (node (ref "C46") (pin "2") (pinfunction "2_2") (pintype "passive"))
      (node (ref "U8") (pin "10") (pinfunction "VREG_10") (pintype "input"))
    )
    (net (code "214") (name "Net-(U9-CP1)") (class "Default")
      (node (ref "C48") (pin "1") (pinfunction "1_1") (pintype "passive"))
      (node (ref "U9") (pin "7") (pinfunction "CP1_7") (pintype "bidirectional"))
    )
    (net (code "215") (name "Net-(U9-CP2)") (class "Default")
      (node (ref "C48") (pin "2") (pinfunction "2_2") (pintype "passive"))
      (node (ref "U9") (pin "8") (pinfunction "CP2_8") (pintype "bidirectional"))
    )
    (net (code "216") (name "Net-(U9-OUT1A)") (class "Default")
      (node (ref "U9") (pin "27") (pinfunction "OUT1A_27") (pintype "output"))
      (node (ref "X7") (pin "3") (pinfunction "1_3") (pintype "passive"))
    )
    (net (code "217") (name "Net-(U9-OUT1B)") (class "Default")
      (node (ref "U9") (pin "24") (pinfunction "OUT1B_24") (pintype "output"))
      (node (ref "X7") (pin "4") (pinfunction "1_4") (pintype "passive"))
    )
    (net (code "218") (name "Net-(U9-OUT2A)") (class "Default")
      (node (ref "U9") (pin "30") (pinfunction "OUT2A_30") (pintype "output"))
      (node (ref "X7") (pin "2") (pinfunction "1_2") (pintype "passive"))
    )
    (net (code "219") (name "Net-(U9-OUT2B)") (class "Default")
      (node (ref "U9") (pin "1") (pinfunction "OUT2B_1") (pintype "output"))
      (node (ref "X7") (pin "1") (pinfunction "1_1") (pintype "passive"))
    )
    (net (code "220") (name "Net-(U9-RESET)") (class "Default")
      (node (ref "C4") (pin "1") (pinfunction "1_1") (pintype "passive"))
      (node (ref "R68") (pin "1") (pinfunction "1_1") (pintype "passive"))
      (node (ref "U9") (pin "13") (pinfunction "RESET_13") (pintype "input"))
      (node (ref "U9") (pin "15") (pinfunction "SLEEP_15") (pintype "input"))
      (node (ref "U9") (pin "16") (pinfunction "VDD_16") (pintype "power_in"))
    )
    (net (code "221") (name "Net-(U9-ROSC)") (class "Default")
      (node (ref "R26") (pin "2") (pinfunction "2_2") (pintype "passive"))
      (node (ref "U9") (pin "14") (pinfunction "ROSC_14") (pintype "input"))
    )
    (net (code "222") (name "Net-(U9-SENSE1)") (class "Default")
      (node (ref "R24") (pin "1") (pinfunction "1_1") (pintype "passive"))
      (node (ref "U9") (pin "25") (pinfunction "SENSE1_25") (pintype "input"))
    )
    (net (code "223") (name "Net-(U9-SENSE2)") (class "Default")
      (node (ref "R23") (pin "1") (pinfunction "1_1") (pintype "passive"))
      (node (ref "U9") (pin "32") (pinfunction "SENSE2_32") (pintype "input"))
    )
    (net (code "224") (name "Net-(U9-VCP)") (class "Default")
      (node (ref "C47") (pin "2") (pinfunction "2_2") (pintype "passive"))
      (node (ref "U9") (pin "9") (pinfunction "VCP_9") (pintype "bidirectional"))
    )
    (net (code "225") (name "Net-(U9-VREG)") (class "Default")
      (node (ref "C51") (pin "2") (pinfunction "2_2") (pintype "passive"))
      (node (ref "U9") (pin "10") (pinfunction "VREG_10") (pintype "input"))
    )
    (net (code "226") (name "Net-(U10-VOC)") (class "Default")
      (node (ref "R34") (pin "1") (pinfunction "1_1") (pintype "passive"))
      (node (ref "U10") (pin "12") (pinfunction "VOC_12") (pintype "bidirectional"))
    )
    (net (code "227") (name "Net-(X3B-S)") (class "Default")
      (node (ref "R27") (pin "1") (pinfunction "1_1") (pintype "passive"))
      (node (ref "R39") (pin "2") (pinfunction "2_2") (pintype "passive"))
      (node (ref "X3") (pin "2") (pinfunction "S_2") (pintype "passive"))
    )
    (net (code "228") (name "Net-(X27B-S)") (class "Default")
      (node (ref "R31") (pin "1") (pinfunction "1_1") (pintype "passive"))
      (node (ref "R32") (pin "2") (pinfunction "2_2") (pintype "passive"))
      (node (ref "X27") (pin "2") (pinfunction "S_2") (pintype "passive"))
    )
    (net (code "229") (name "Net-(X28B-S)") (class "Default")
      (node (ref "R36") (pin "1") (pinfunction "1_1") (pintype "passive"))
      (node (ref "R37") (pin "2") (pinfunction "2_2") (pintype "passive"))
      (node (ref "X28") (pin "2") (pinfunction "S_2") (pintype "passive"))
    )
    (net (code "230") (name "Net-(X29B-S)") (class "Default")
      (node (ref "R28") (pin "2") (pinfunction "2_2") (pintype "passive"))
      (node (ref "R38") (pin "1") (pinfunction "1_1") (pintype "passive"))
      (node (ref "X29") (pin "2") (pinfunction "S_2") (pintype "passive"))
    )
    (net (code "231") (name "Net-(X33C-1)") (class "Default")
      (node (ref "F3") (pin "P$1") (pinfunction "P$1_P$1") (pintype "bidirectional"))
      (node (ref "X33") (pin "3") (pinfunction "1_3") (pintype "passive"))
    )
    (net (code "232") (name "VCC") (class "Default")
      (node (ref "C25") (pin "1") (pinfunction "1_1") (pintype "passive"))
      (node (ref "C30") (pin "1") (pinfunction "1_1") (pintype "passive"))
      (node (ref "C52") (pin "1") (pinfunction "1_1") (pintype "passive"))
      (node (ref "C53") (pin "1") (pinfunction "1_1") (pintype "passive"))
      (node (ref "C55") (pin "1") (pinfunction "1_1") (pintype "passive"))
      (node (ref "C68") (pin "2") (pinfunction "2_2") (pintype "passive"))
      (node (ref "C69") (pin "1") (pinfunction "1_1") (pintype "passive"))
      (node (ref "C7") (pin "1") (pinfunction "1_1") (pintype "passive"))
      (node (ref "C8") (pin "1") (pinfunction "1_1") (pintype "passive"))
      (node (ref "C9") (pin "1") (pinfunction "1_1") (pintype "passive"))
      (node (ref "D5") (pin "C") (pinfunction "C_C") (pintype "passive"))
      (node (ref "L2") (pin "1") (pinfunction "1_1") (pintype "passive"))
      (node (ref "L3") (pin "P$2") (pinfunction "2_P$2") (pintype "passive"))
      (node (ref "R13") (pin "2") (pinfunction "2_2") (pintype "passive"))
      (node (ref "R27") (pin "2") (pinfunction "2_2") (pintype "passive"))
      (node (ref "R29") (pin "2") (pinfunction "2_2") (pintype "passive"))
      (node (ref "R30") (pin "1") (pinfunction "1_1") (pintype "passive"))
      (node (ref "R31") (pin "2") (pinfunction "2_2") (pintype "passive"))
      (node (ref "R35") (pin "1") (pinfunction "1_1") (pintype "passive"))
      (node (ref "R36") (pin "2") (pinfunction "2_2") (pintype "passive"))
      (node (ref "R38") (pin "2") (pinfunction "2_2") (pintype "passive"))
      (node (ref "R44") (pin "2") (pinfunction "2_2") (pintype "passive"))
      (node (ref "R45") (pin "2") (pinfunction "2_2") (pintype "passive"))
      (node (ref "R46") (pin "2") (pinfunction "2_2") (pintype "passive"))
      (node (ref "R59") (pin "1") (pinfunction "1_1") (pintype "passive"))
      (node (ref "R60") (pin "1") (pinfunction "1_1") (pintype "passive"))
      (node (ref "R61") (pin "1") (pinfunction "1_1") (pintype "passive"))
      (node (ref "R62") (pin "1") (pinfunction "1_1") (pintype "passive"))
      (node (ref "R63") (pin "1") (pinfunction "1_1") (pintype "passive"))
      (node (ref "R65") (pin "2") (pinfunction "2_2") (pintype "passive"))
      (node (ref "R66") (pin "2") (pinfunction "2_2") (pintype "passive"))
      (node (ref "R67") (pin "2") (pinfunction "2_2") (pintype "passive"))
      (node (ref "R68") (pin "2") (pinfunction "2_2") (pintype "passive"))
      (node (ref "U10") (pin "10") (pinfunction "VDD2B_10") (pintype "bidirectional"))
      (node (ref "U10") (pin "16") (pinfunction "VDD2A_16") (pintype "bidirectional"))
      (node (ref "U2") (pin "10") (pinfunction "VCC_10") (pintype "power_in"))
      (node (ref "U2") (pin "31") (pinfunction "VCC1_31") (pintype "power_in"))
      (node (ref "U2") (pin "61") (pinfunction "VCC2_61") (pintype "power_in"))
      (node (ref "U2") (pin "80") (pinfunction "VCC3_80") (pintype "power_in"))
      (node (ref "U4") (pin "P06") (pinfunction "VDD_P06") (pintype "bidirectional"))
      (node (ref "X1") (pin "2") (pinfunction "S_2") (pintype "passive"))
      (node (ref "X10") (pin "1") (pinfunction "S_1") (pintype "passive"))
      (node (ref "X12") (pin "1") (pinfunction "1_1") (pintype "passive"))
      (node (ref "X13") (pin "1") (pinfunction "1_1") (pintype "passive"))
      (node (ref "X13") (pin "2") (pinfunction "2_2") (pintype "passive"))
      (node (ref "X18") (pin "2") (pinfunction "2_2") (pintype "passive"))
      (node (ref "X20") (pin "1") (pinfunction "1_1") (pintype "passive"))
      (node (ref "X21") (pin "3") (pinfunction "S_3") (pintype "passive"))
      (node (ref "X22") (pin "3") (pinfunction "S_3") (pintype "passive"))
      (node (ref "X23") (pin "3") (pinfunction "S_3") (pintype "passive"))
      (node (ref "X24") (pin "3") (pinfunction "S_3") (pintype "passive"))
      (node (ref "X25") (pin "3") (pinfunction "S_3") (pintype "passive"))
      (node (ref "X26") (pin "3") (pinfunction "S_3") (pintype "passive"))
      (node (ref "X31") (pin "1") (pinfunction "1_1") (pintype "passive"))
      (node (ref "X32") (pin "1") (pinfunction "1_1") (pintype "passive"))
      (node (ref "X34") (pin "1") (pinfunction "1_1") (pintype "passive"))
      (node (ref "X39") (pin "1") (pinfunction "1_1") (pintype "passive"))
      (node (ref "X40") (pin "1") (pinfunction "1_1") (pintype "passive"))
      (node (ref "X5") (pin "2") (pinfunction "S_2") (pintype "passive"))
    )
    (net (code "233") (name "unconnected-(RN5-Pad1)") (class "Default")
      (node (ref "RN5") (pin "1") (pinfunction "1_1") (pintype "passive"))
    )
    (net (code "234") (name "unconnected-(RN5A-2-Pad8)") (class "Default")
      (node (ref "RN5") (pin "8") (pinfunction "2_8") (pintype "passive"))
    )
    (net (code "235") (name "unconnected-(U3-NC-Pad2)") (class "Default")
      (node (ref "U3") (pin "2") (pinfunction "NC_2") (pintype "bidirectional"))
    )
    (net (code "236") (name "unconnected-(U3-NC1-Pad3)") (class "Default")
      (node (ref "U3") (pin "3") (pinfunction "NC1_3") (pintype "bidirectional"))
    )
    (net (code "237") (name "unconnected-(U5-NC1-Pad2)") (class "Default")
      (node (ref "U5") (pin "2") (pinfunction "NC1_2") (pintype "output"))
    )
    (net (code "238") (name "unconnected-(U5-NC2-Pad4)") (class "Default")
      (node (ref "U5") (pin "4") (pinfunction "NC2_4") (pintype "output"))
    )
    (net (code "239") (name "unconnected-(U5-NC3-Pad21)") (class "Default")
      (node (ref "U5") (pin "21") (pinfunction "NC3_21") (pintype "output"))
    )
    (net (code "240") (name "unconnected-(U5-NC4-Pad23)") (class "Default")
      (node (ref "U5") (pin "23") (pinfunction "NC4_23") (pintype "output"))
    )
    (net (code "241") (name "unconnected-(U5-NC5-Pad26)") (class "Default")
      (node (ref "U5") (pin "26") (pinfunction "NC5_26") (pintype "output"))
    )
    (net (code "242") (name "unconnected-(U5-NC6-Pad28)") (class "Default")
      (node (ref "U5") (pin "28") (pinfunction "NC6_28") (pintype "output"))
    )
    (net (code "243") (name "unconnected-(U5-NC7-Pad29)") (class "Default")
      (node (ref "U5") (pin "29") (pinfunction "NC7_29") (pintype "output"))
    )
    (net (code "244") (name "unconnected-(U5-NC8-Pad31)") (class "Default")
      (node (ref "U5") (pin "31") (pinfunction "NC8_31") (pintype "output"))
    )
    (net (code "245") (name "unconnected-(U6-NC1-Pad2)") (class "Default")
      (node (ref "U6") (pin "2") (pinfunction "NC1_2") (pintype "output"))
    )
    (net (code "246") (name "unconnected-(U6-NC2-Pad4)") (class "Default")
      (node (ref "U6") (pin "4") (pinfunction "NC2_4") (pintype "output"))
    )
    (net (code "247") (name "unconnected-(U6-NC3-Pad21)") (class "Default")
      (node (ref "U6") (pin "21") (pinfunction "NC3_21") (pintype "output"))
    )
    (net (code "248") (name "unconnected-(U6-NC4-Pad23)") (class "Default")
      (node (ref "U6") (pin "23") (pinfunction "NC4_23") (pintype "output"))
    )
    (net (code "249") (name "unconnected-(U6-NC5-Pad26)") (class "Default")
      (node (ref "U6") (pin "26") (pinfunction "NC5_26") (pintype "output"))
    )
    (net (code "250") (name "unconnected-(U6-NC6-Pad28)") (class "Default")
      (node (ref "U6") (pin "28") (pinfunction "NC6_28") (pintype "output"))
    )
    (net (code "251") (name "unconnected-(U6-NC7-Pad29)") (class "Default")
      (node (ref "U6") (pin "29") (pinfunction "NC7_29") (pintype "output"))
    )
    (net (code "252") (name "unconnected-(U6-NC8-Pad31)") (class "Default")
      (node (ref "U6") (pin "31") (pinfunction "NC8_31") (pintype "output"))
    )
    (net (code "253") (name "unconnected-(U7-NC1-Pad2)") (class "Default")
      (node (ref "U7") (pin "2") (pinfunction "NC1_2") (pintype "output"))
    )
    (net (code "254") (name "unconnected-(U7-NC2-Pad4)") (class "Default")
      (node (ref "U7") (pin "4") (pinfunction "NC2_4") (pintype "output"))
    )
    (net (code "255") (name "unconnected-(U7-NC3-Pad21)") (class "Default")
      (node (ref "U7") (pin "21") (pinfunction "NC3_21") (pintype "output"))
    )
    (net (code "256") (name "unconnected-(U7-NC4-Pad23)") (class "Default")
      (node (ref "U7") (pin "23") (pinfunction "NC4_23") (pintype "output"))
    )
    (net (code "257") (name "unconnected-(U7-NC5-Pad26)") (class "Default")
      (node (ref "U7") (pin "26") (pinfunction "NC5_26") (pintype "output"))
    )
    (net (code "258") (name "unconnected-(U7-NC6-Pad28)") (class "Default")
      (node (ref "U7") (pin "28") (pinfunction "NC6_28") (pintype "output"))
    )
    (net (code "259") (name "unconnected-(U7-NC7-Pad29)") (class "Default")
      (node (ref "U7") (pin "29") (pinfunction "NC7_29") (pintype "output"))
    )
    (net (code "260") (name "unconnected-(U7-NC8-Pad31)") (class "Default")
      (node (ref "U7") (pin "31") (pinfunction "NC8_31") (pintype "output"))
    )
    (net (code "261") (name "unconnected-(U8-NC1-Pad2)") (class "Default")
      (node (ref "U8") (pin "2") (pinfunction "NC1_2") (pintype "output"))
    )
    (net (code "262") (name "unconnected-(U8-NC2-Pad4)") (class "Default")
      (node (ref "U8") (pin "4") (pinfunction "NC2_4") (pintype "output"))
    )
    (net (code "263") (name "unconnected-(U8-NC3-Pad21)") (class "Default")
      (node (ref "U8") (pin "21") (pinfunction "NC3_21") (pintype "output"))
    )
    (net (code "264") (name "unconnected-(U8-NC4-Pad23)") (class "Default")
      (node (ref "U8") (pin "23") (pinfunction "NC4_23") (pintype "output"))
    )
    (net (code "265") (name "unconnected-(U8-NC5-Pad26)") (class "Default")
      (node (ref "U8") (pin "26") (pinfunction "NC5_26") (pintype "output"))
    )
    (net (code "266") (name "unconnected-(U8-NC6-Pad28)") (class "Default")
      (node (ref "U8") (pin "28") (pinfunction "NC6_28") (pintype "output"))
    )
    (net (code "267") (name "unconnected-(U8-NC7-Pad29)") (class "Default")
      (node (ref "U8") (pin "29") (pinfunction "NC7_29") (pintype "output"))
    )
    (net (code "268") (name "unconnected-(U8-NC8-Pad31)") (class "Default")
      (node (ref "U8") (pin "31") (pinfunction "NC8_31") (pintype "output"))
    )
    (net (code "269") (name "unconnected-(U9-NC1-Pad2)") (class "Default")
      (node (ref "U9") (pin "2") (pinfunction "NC1_2") (pintype "output"))
    )
    (net (code "270") (name "unconnected-(U9-NC2-Pad4)") (class "Default")
      (node (ref "U9") (pin "4") (pinfunction "NC2_4") (pintype "output"))
    )
    (net (code "271") (name "unconnected-(U9-NC3-Pad21)") (class "Default")
      (node (ref "U9") (pin "21") (pinfunction "NC3_21") (pintype "output"))
    )
    (net (code "272") (name "unconnected-(U9-NC4-Pad23)") (class "Default")
      (node (ref "U9") (pin "23") (pinfunction "NC4_23") (pintype "output"))
    )
    (net (code "273") (name "unconnected-(U9-NC5-Pad26)") (class "Default")
      (node (ref "U9") (pin "26") (pinfunction "NC5_26") (pintype "output"))
    )
    (net (code "274") (name "unconnected-(U9-NC6-Pad28)") (class "Default")
      (node (ref "U9") (pin "28") (pinfunction "NC6_28") (pintype "output"))
    )
    (net (code "275") (name "unconnected-(U9-NC7-Pad29)") (class "Default")
      (node (ref "U9") (pin "29") (pinfunction "NC7_29") (pintype "output"))
    )
    (net (code "276") (name "unconnected-(U9-NC8-Pad31)") (class "Default")
      (node (ref "U9") (pin "31") (pinfunction "NC8_31") (pintype "output"))
    )
    (net (code "277") (name "unconnected-(U10-VOB-Pad13)") (class "Default")
      (node (ref "U10") (pin "13") (pinfunction "VOB_13") (pintype "bidirectional"))
    )
    (net (code "278") (name "unconnected-(X12-Pad8)") (class "Default")
      (node (ref "X12") (pin "8") (pinfunction "8_8") (pintype "passive"))
    )
  )
)
